# TR4.net
KiCad netlist of a schematic drawn in EAGLE
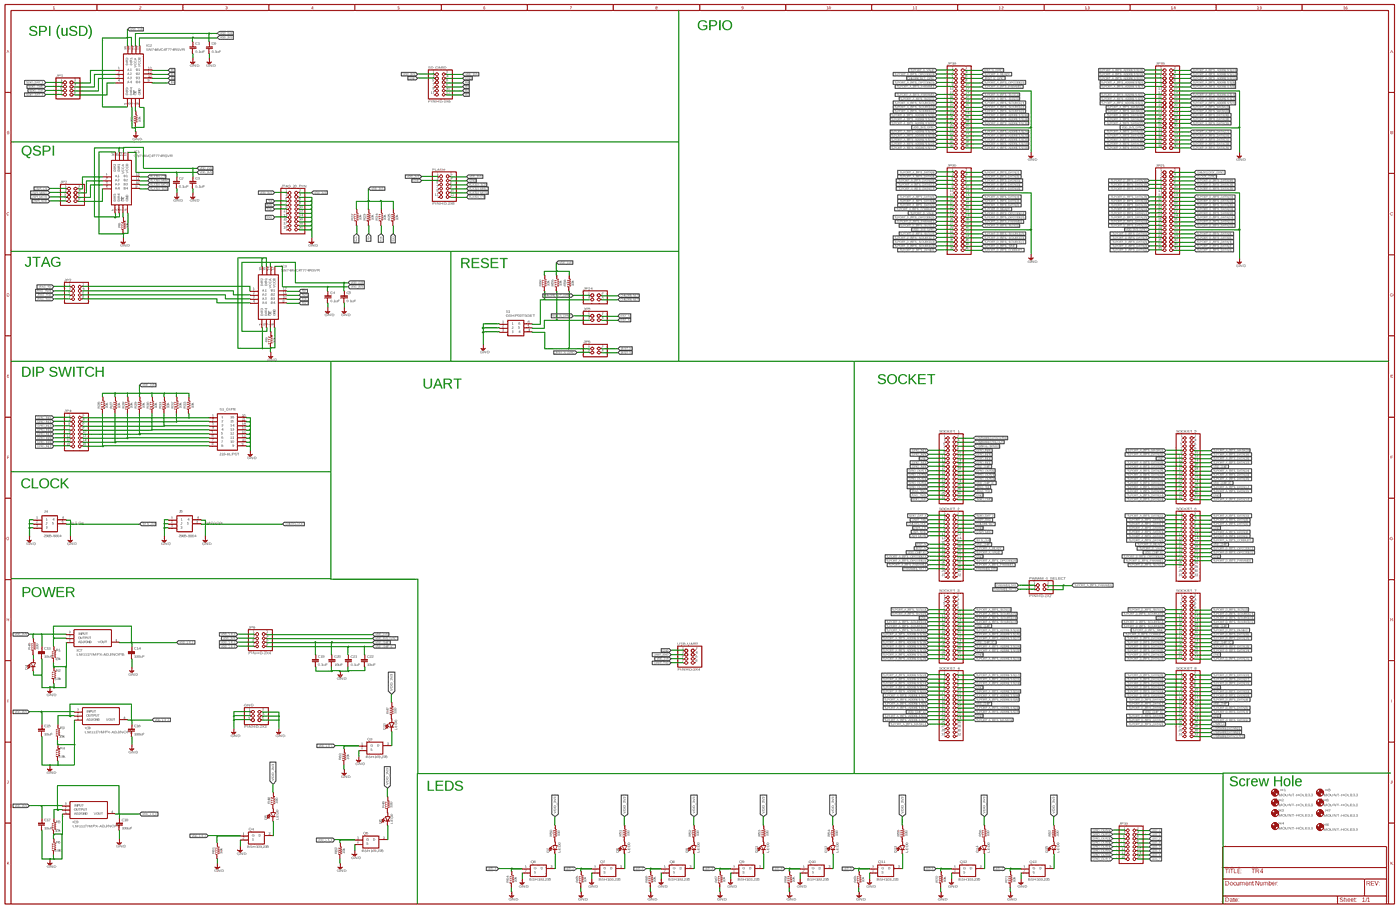
[diagram p0: schematic, sheet 1, overview]
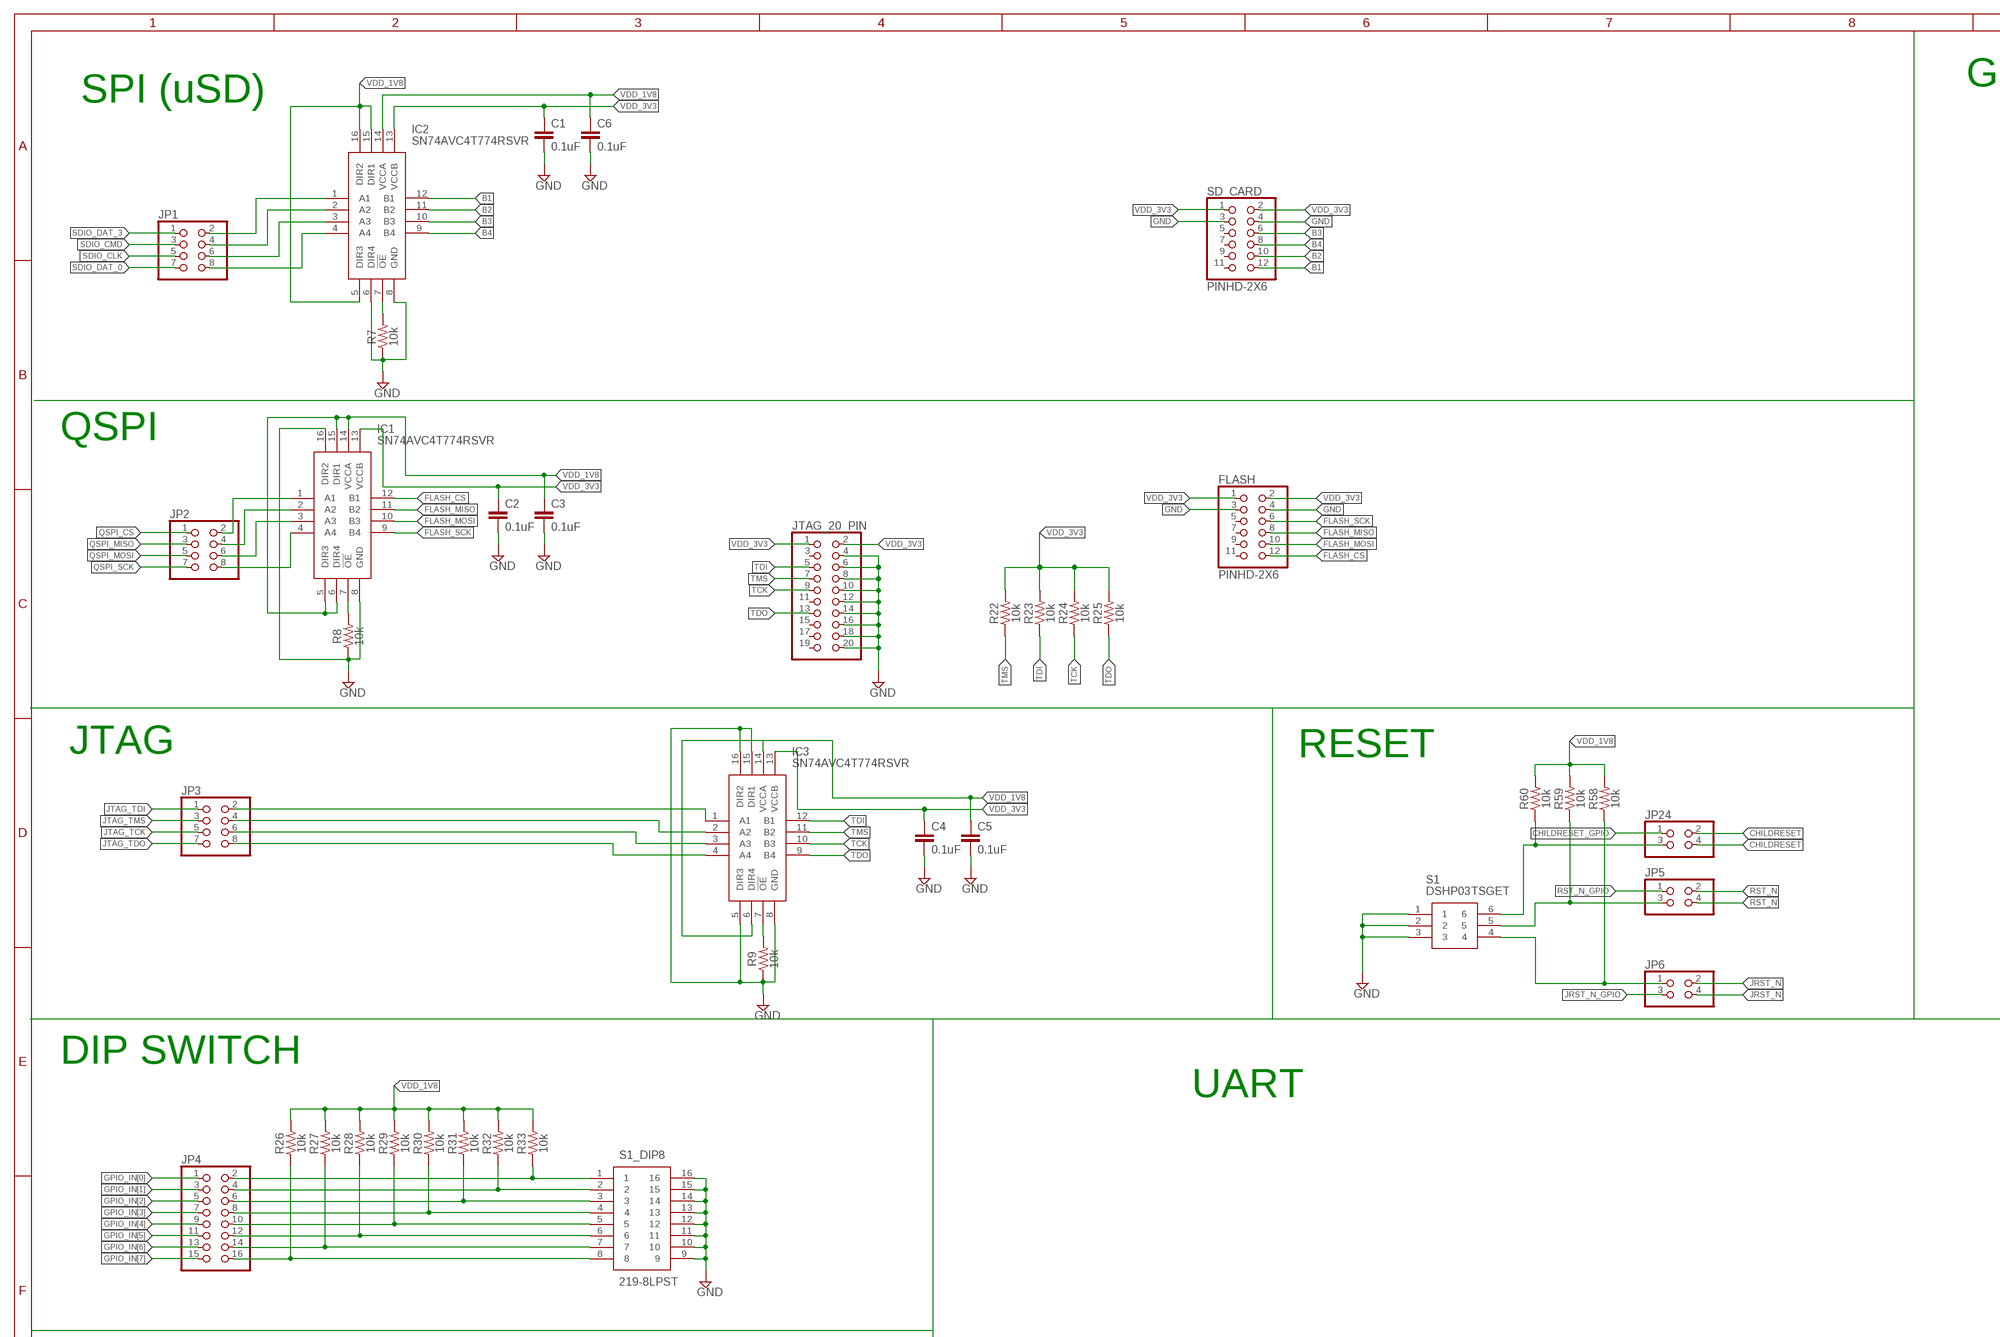
[diagram p1: schematic, sheet 1, part 1 of 4]
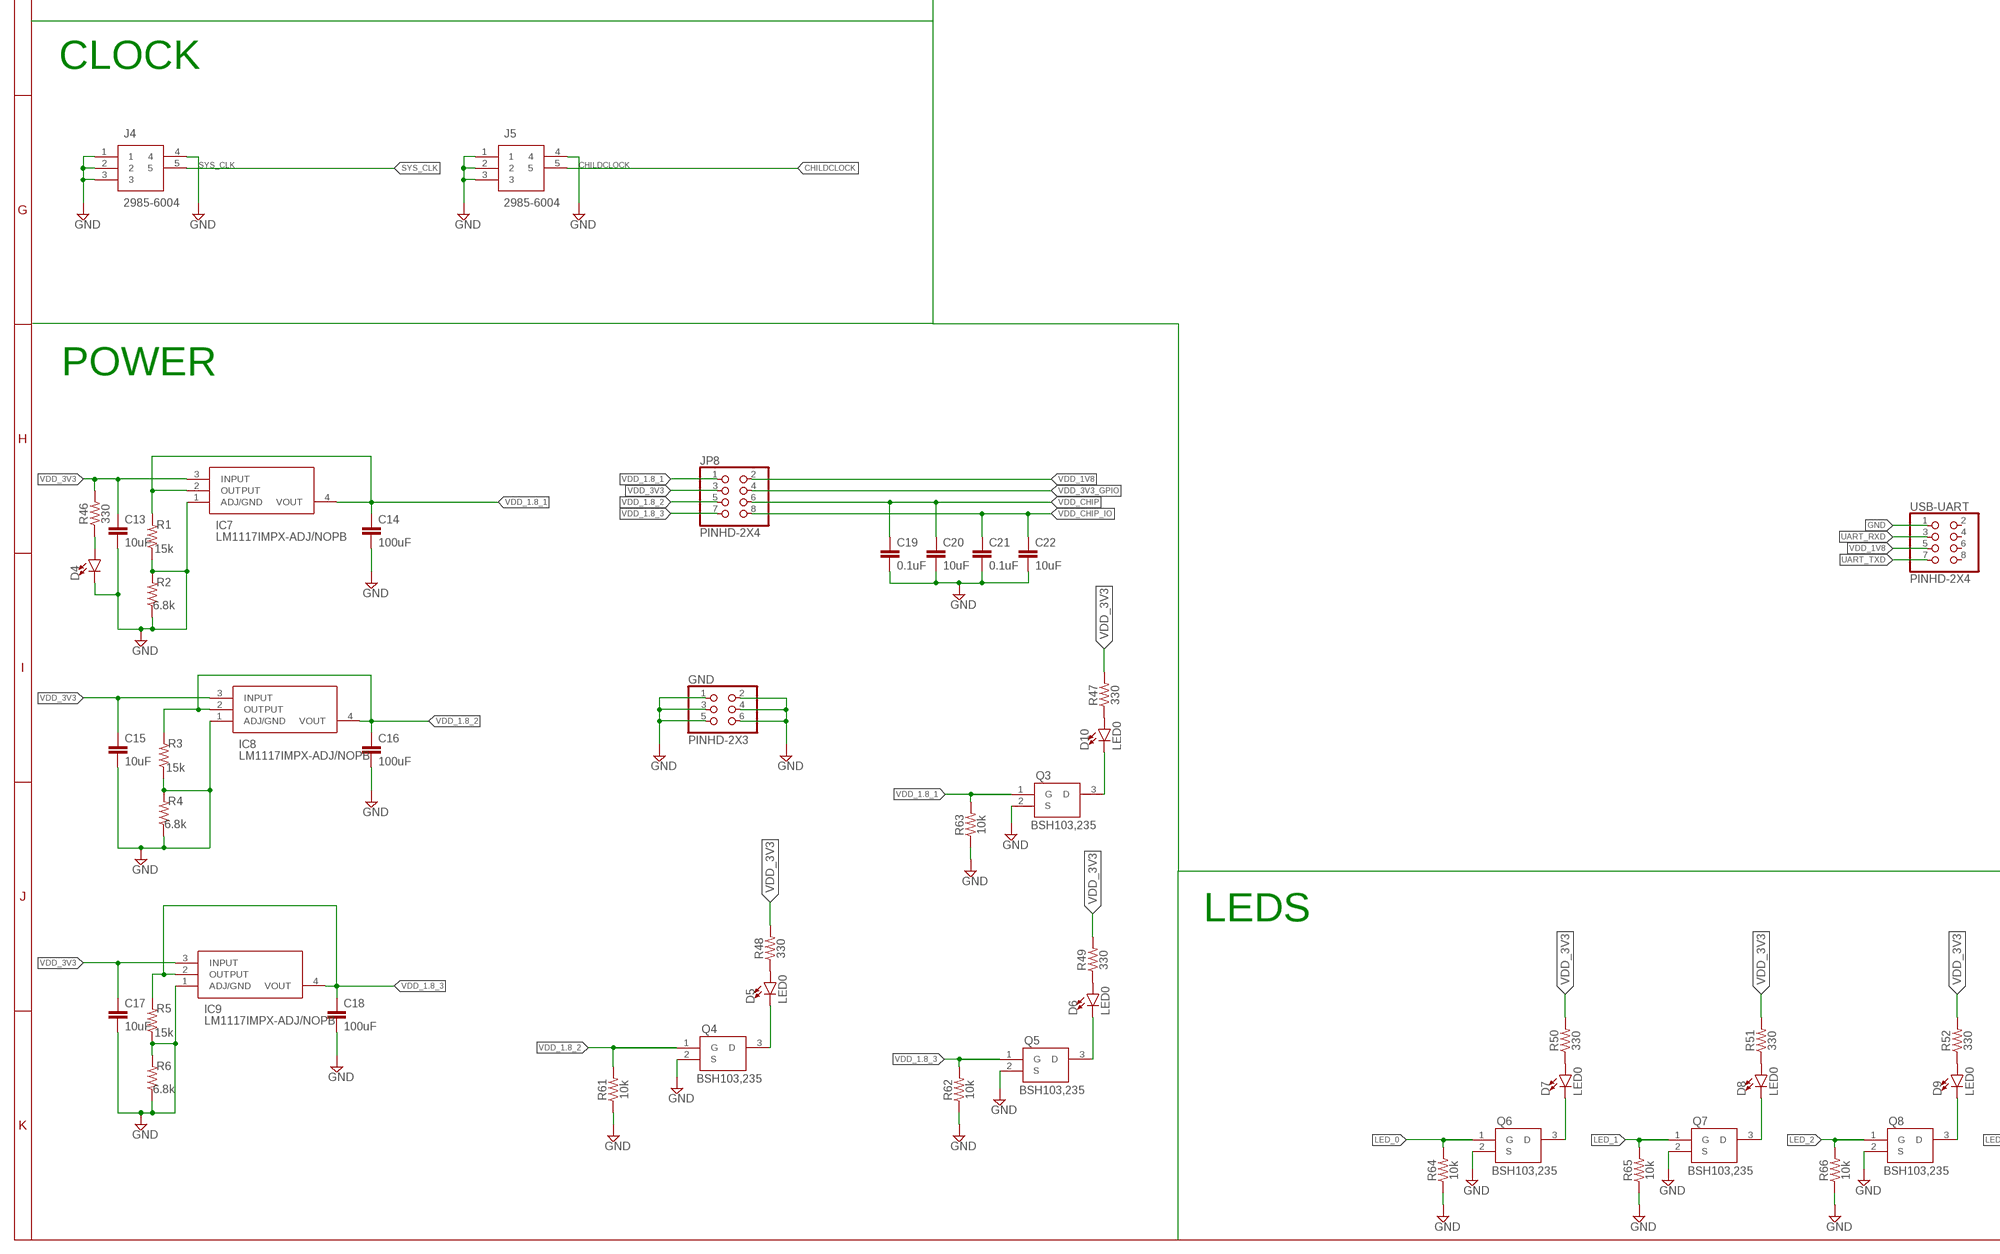
[diagram p2: schematic, sheet 1, part 2 of 4]
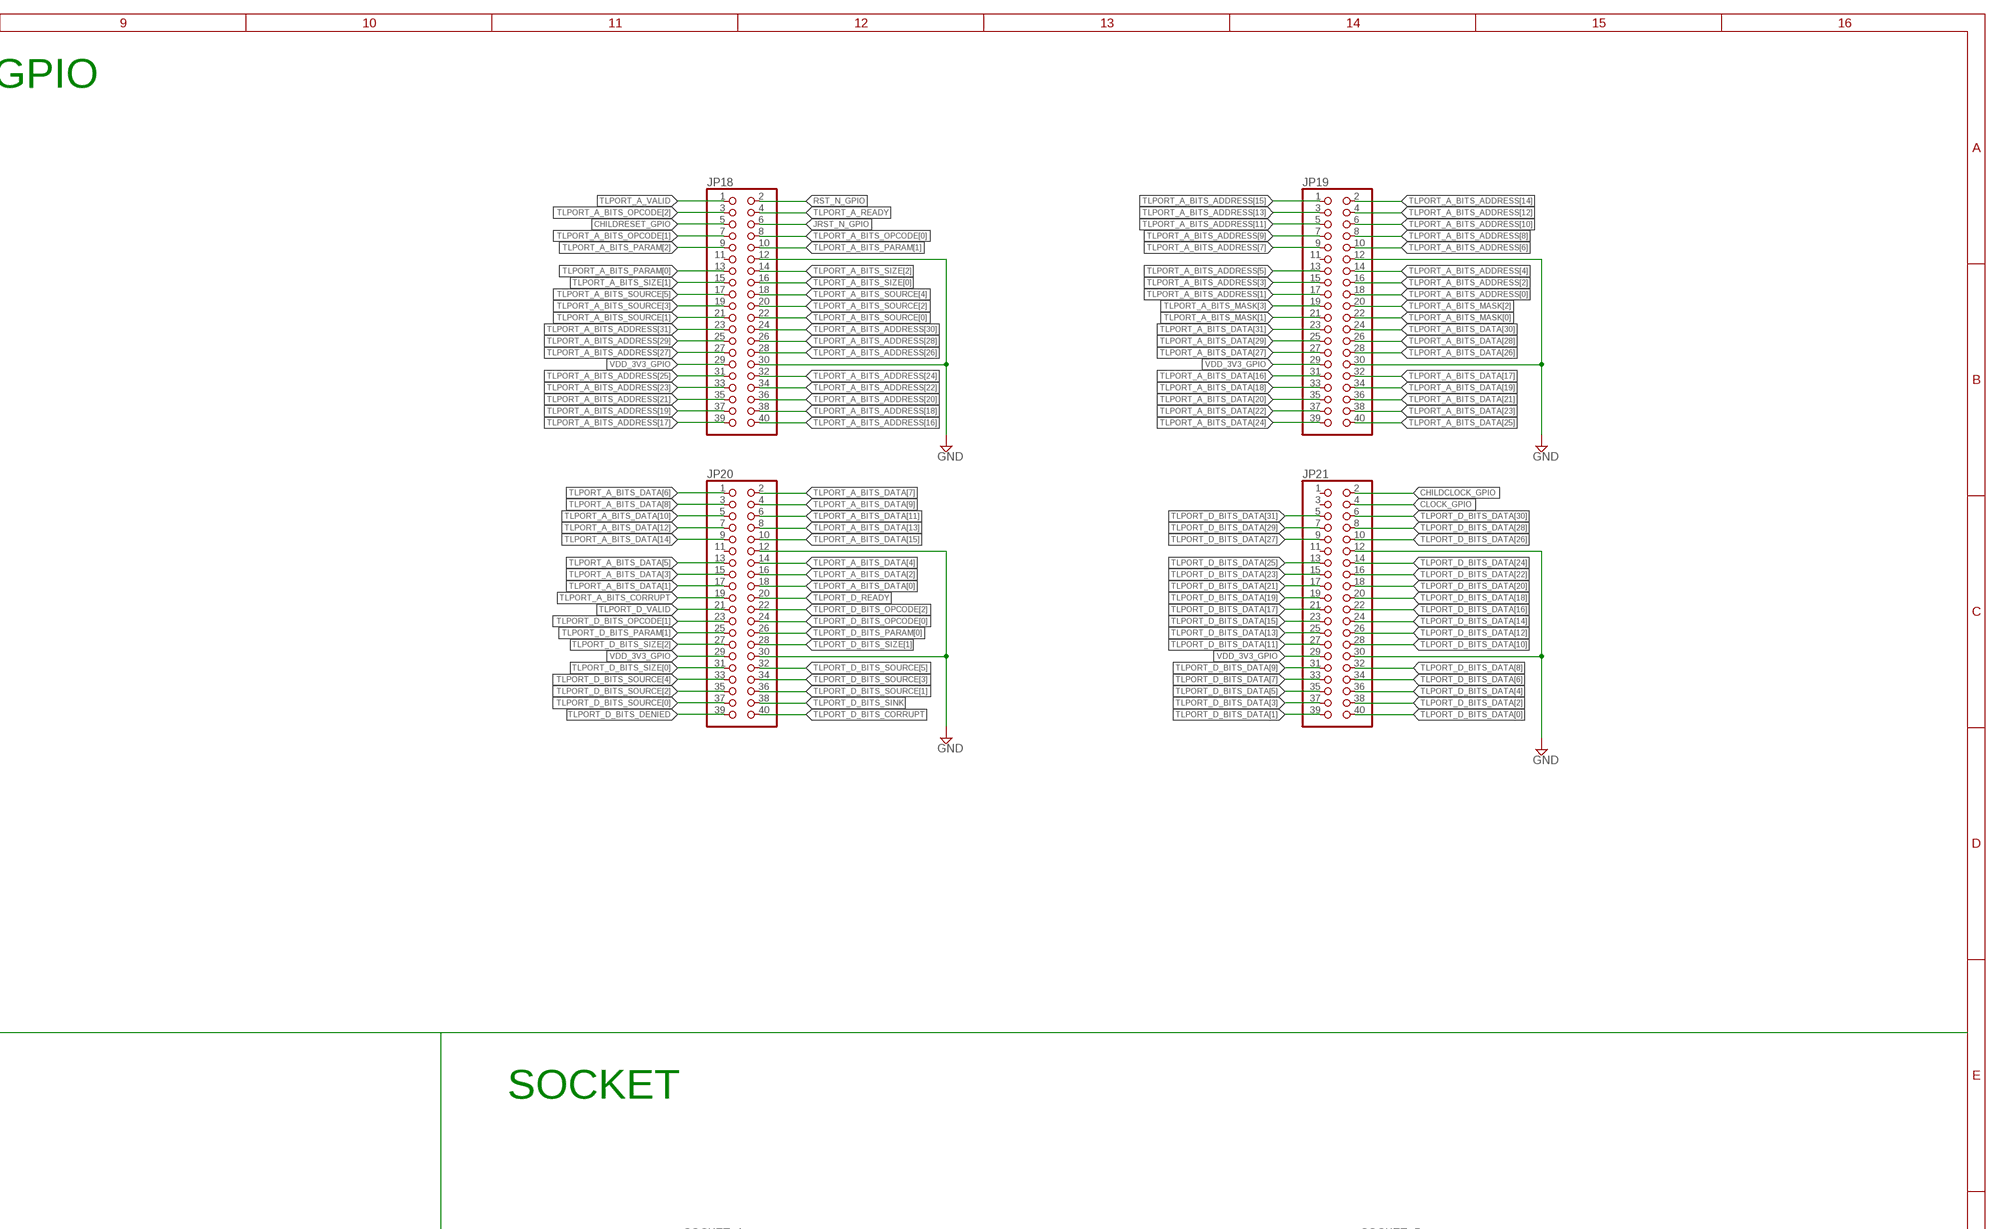
[diagram p3: schematic, sheet 1, part 3 of 4]
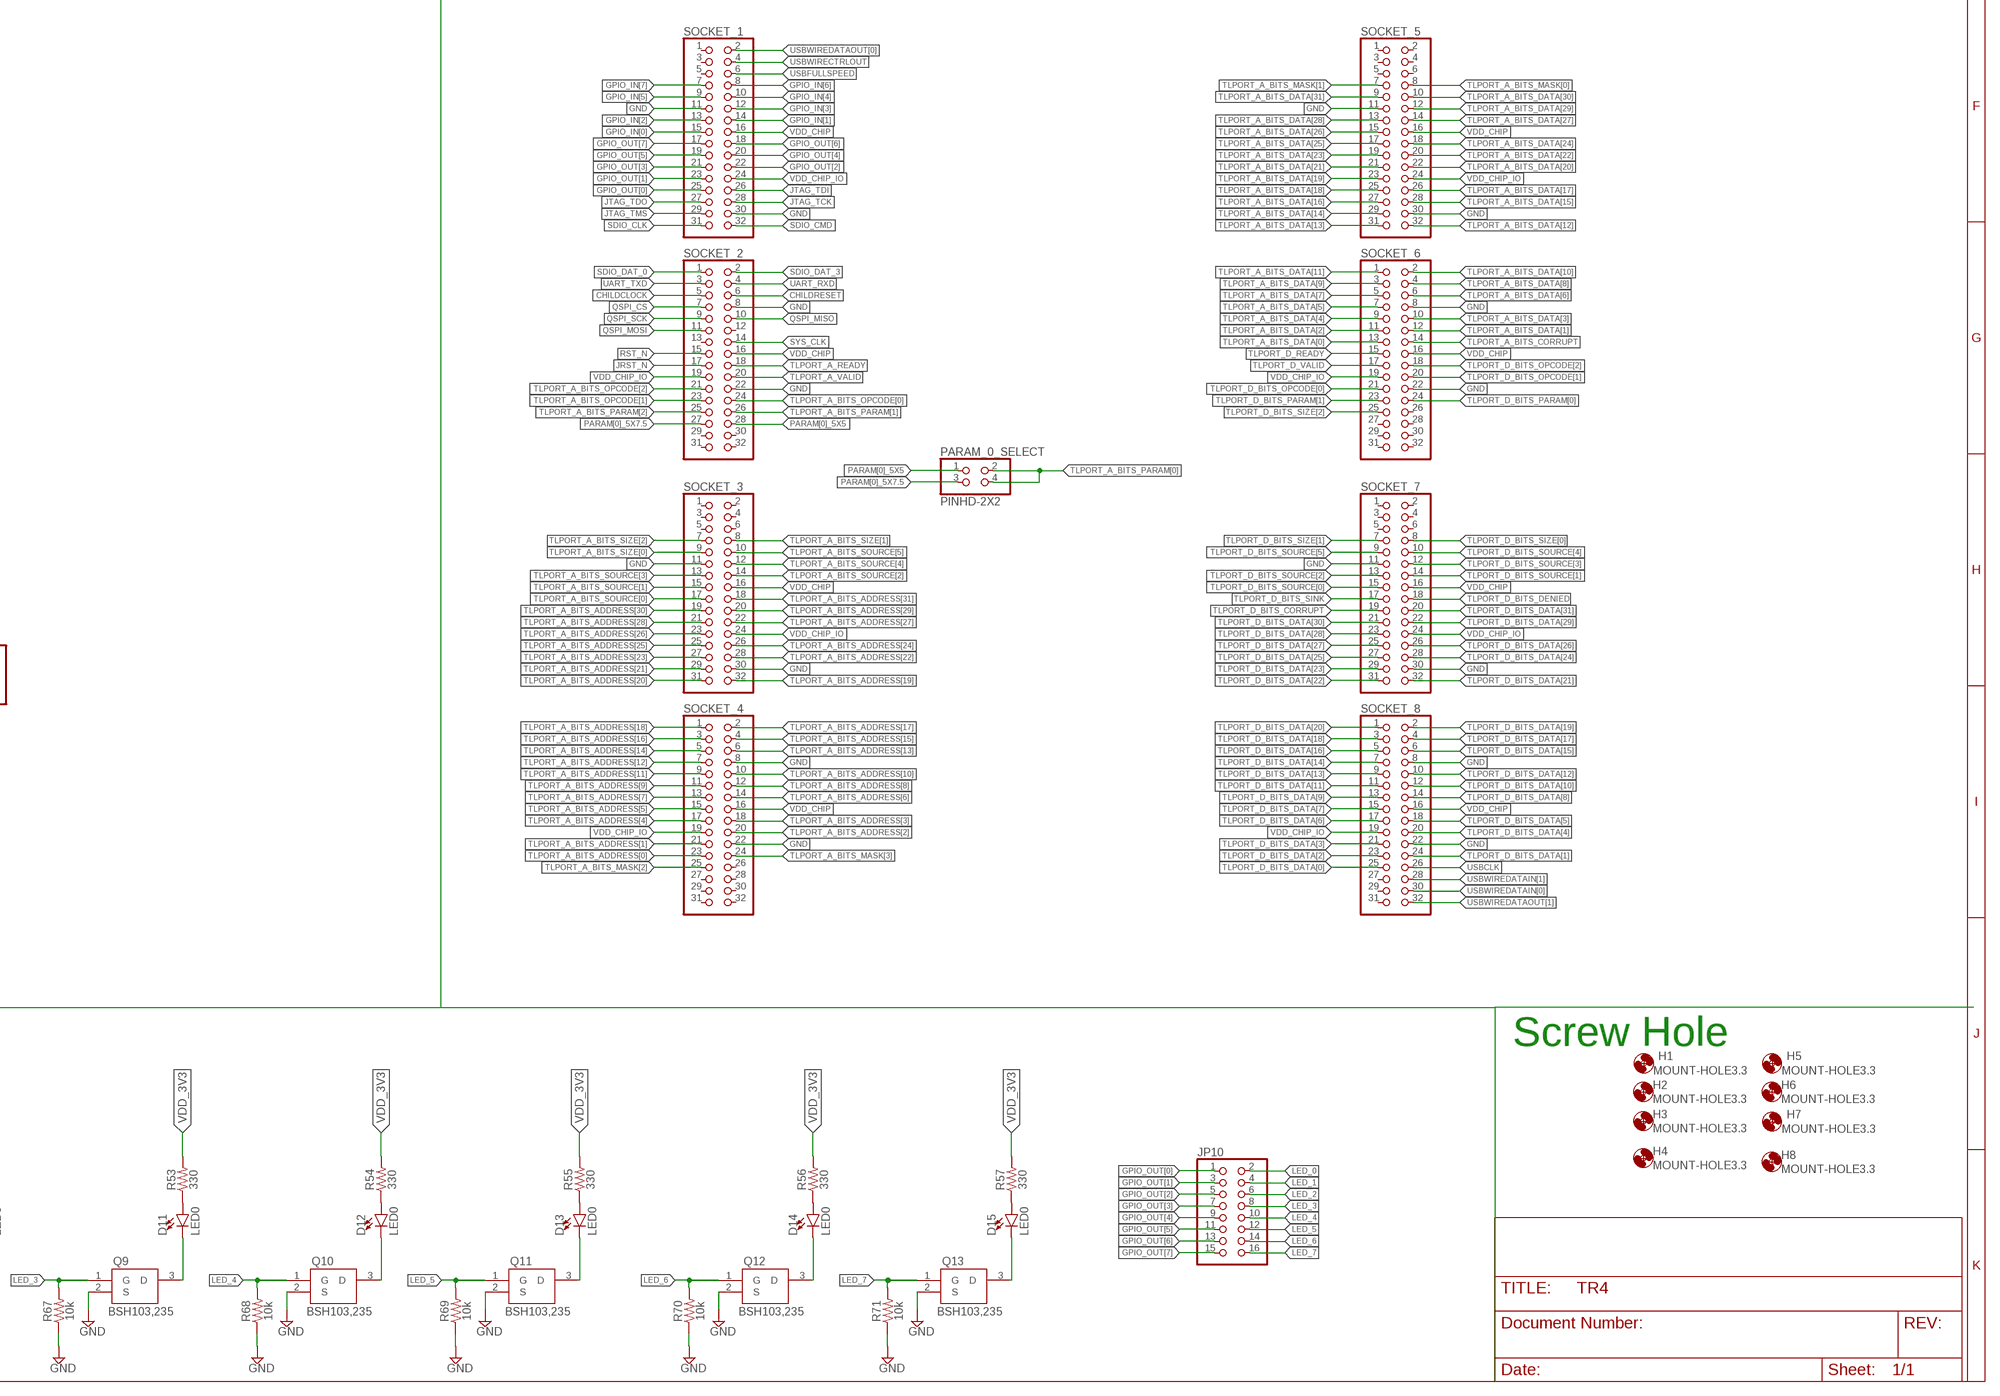
[diagram p4: schematic, sheet 1, part 4 of 4]

(export (version "E")
  (design (tool "Eeschema 10.0.6"))
  (components
    (comp (ref "C1")
      (value "0.1uF")
      (footprint "eagle-import:0603")
      (libsource (lib "eagle-import") (part "0.1UF-0603-25V-5%"))
    )
    (comp (ref "C2")
      (value "0.1uF")
      (footprint "eagle-import:0603")
      (libsource (lib "eagle-import") (part "0.1UF-0603-25V-5%"))
    )
    (comp (ref "C3")
      (value "0.1uF")
      (footprint "eagle-import:0603")
      (libsource (lib "eagle-import") (part "0.1UF-0603-25V-5%"))
    )
    (comp (ref "C4")
      (value "0.1uF")
      (footprint "eagle-import:0603")
      (libsource (lib "eagle-import") (part "0.1UF-0603-25V-5%"))
    )
    (comp (ref "C5")
      (value "0.1uF")
      (footprint "eagle-import:0603")
      (libsource (lib "eagle-import") (part "0.1UF-0603-25V-5%"))
    )
    (comp (ref "C6")
      (value "0.1uF")
      (footprint "eagle-import:0603")
      (libsource (lib "eagle-import") (part "0.1UF-0603-25V-5%"))
    )
    (comp (ref "C13")
      (value "10uF")
      (footprint "eagle-import:0603")
      (libsource (lib "eagle-import") (part "10UF-0603-6.3V-20%"))
    )
    (comp (ref "C14")
      (value "100uF")
      (footprint "eagle-import:0603")
      (libsource (lib "eagle-import") (part "10UF-0603-6.3V-20%"))
    )
    (comp (ref "C15")
      (value "10uF")
      (footprint "eagle-import:0603")
      (libsource (lib "eagle-import") (part "10UF-0603-6.3V-20%"))
    )
    (comp (ref "C16")
      (value "100uF")
      (footprint "eagle-import:0603")
      (libsource (lib "eagle-import") (part "10UF-0603-6.3V-20%"))
    )
    (comp (ref "C17")
      (value "10uF")
      (footprint "eagle-import:0603")
      (libsource (lib "eagle-import") (part "10UF-0603-6.3V-20%"))
    )
    (comp (ref "C18")
      (value "100uF")
      (footprint "eagle-import:0603")
      (libsource (lib "eagle-import") (part "10UF-0603-6.3V-20%"))
    )
    (comp (ref "C19")
      (value "0.1uF")
      (footprint "eagle-import:0603")
      (libsource (lib "eagle-import") (part "0.1UF-0603-25V-5%"))
    )
    (comp (ref "C20")
      (value "10uF")
      (footprint "eagle-import:0603")
      (libsource (lib "eagle-import") (part "10UF-0603-6.3V-20%"))
    )
    (comp (ref "C21")
      (value "0.1uF")
      (footprint "eagle-import:0603")
      (libsource (lib "eagle-import") (part "0.1UF-0603-25V-5%"))
    )
    (comp (ref "C22")
      (value "10uF")
      (footprint "eagle-import:0603")
      (libsource (lib "eagle-import") (part "10UF-0603-6.3V-20%"))
    )
    (comp (ref "D4")
      (value "LED0603")
      (footprint "eagle-import:LED-0603")
      (libsource (lib "eagle-import") (part "LED0603"))
    )
    (comp (ref "D5")
      (value "LED0")
      (footprint "eagle-import:LED-0603")
      (libsource (lib "eagle-import") (part "LED0603"))
    )
    (comp (ref "D6")
      (value "LED0")
      (footprint "eagle-import:LED-0603")
      (libsource (lib "eagle-import") (part "LED0603"))
    )
    (comp (ref "D7")
      (value "LED0")
      (footprint "eagle-import:LED-0603")
      (libsource (lib "eagle-import") (part "LED0603"))
    )
    (comp (ref "D8")
      (value "LED0")
      (footprint "eagle-import:LED-0603")
      (libsource (lib "eagle-import") (part "LED0603"))
    )
    (comp (ref "D9")
      (value "LED0")
      (footprint "eagle-import:LED-0603")
      (libsource (lib "eagle-import") (part "LED0603"))
    )
    (comp (ref "D10")
      (value "LED0")
      (footprint "eagle-import:LED-0603")
      (libsource (lib "eagle-import") (part "LED0603"))
    )
    (comp (ref "D11")
      (value "LED0")
      (footprint "eagle-import:LED-0603")
      (libsource (lib "eagle-import") (part "LED0603"))
    )
    (comp (ref "D12")
      (value "LED0")
      (footprint "eagle-import:LED-0603")
      (libsource (lib "eagle-import") (part "LED0603"))
    )
    (comp (ref "D13")
      (value "LED0")
      (footprint "eagle-import:LED-0603")
      (libsource (lib "eagle-import") (part "LED0603"))
    )
    (comp (ref "D14")
      (value "LED0")
      (footprint "eagle-import:LED-0603")
      (libsource (lib "eagle-import") (part "LED0603"))
    )
    (comp (ref "D15")
      (value "LED0")
      (footprint "eagle-import:LED-0603")
      (libsource (lib "eagle-import") (part "LED0603"))
    )
    (comp (ref "FLASH")
      (value "PINHD-2X6")
      (footprint "eagle-import:2X06")
      (libsource (lib "eagle-import") (part "PINHD-2X6"))
    )
    (comp (ref "GND")
      (value "PINHD-2X3")
      (footprint "eagle-import:2X03")
      (libsource (lib "eagle-import") (part "PINHD-2X3"))
    )
    (comp (ref "H1")
      (value "MOUNT-HOLE3.3")
      (footprint "eagle-import:3,3")
      (libsource (lib "eagle-import") (part "MOUNT-HOLE3.3"))
    )
    (comp (ref "H2")
      (value "MOUNT-HOLE3.3")
      (footprint "eagle-import:3,3")
      (libsource (lib "eagle-import") (part "MOUNT-HOLE3.3"))
    )
    (comp (ref "H3")
      (value "MOUNT-HOLE3.3")
      (footprint "eagle-import:3,3")
      (libsource (lib "eagle-import") (part "MOUNT-HOLE3.3"))
    )
    (comp (ref "H4")
      (value "MOUNT-HOLE3.3")
      (footprint "eagle-import:3,3")
      (libsource (lib "eagle-import") (part "MOUNT-HOLE3.3"))
    )
    (comp (ref "H5")
      (value "MOUNT-HOLE3.3")
      (footprint "eagle-import:3,3")
      (libsource (lib "eagle-import") (part "MOUNT-HOLE3.3"))
    )
    (comp (ref "H6")
      (value "MOUNT-HOLE3.3")
      (footprint "eagle-import:3,3")
      (libsource (lib "eagle-import") (part "MOUNT-HOLE3.3"))
    )
    (comp (ref "H7")
      (value "MOUNT-HOLE3.3")
      (footprint "eagle-import:3,3")
      (libsource (lib "eagle-import") (part "MOUNT-HOLE3.3"))
    )
    (comp (ref "H8")
      (value "MOUNT-HOLE3.3")
      (footprint "eagle-import:3,3")
      (libsource (lib "eagle-import") (part "MOUNT-HOLE3.3"))
    )
    (comp (ref "IC1")
      (value "SN74AVC4T774RSVR")
      (footprint "eagle-import:QFN40P180X260X55-16N")
      (fields (field (name "MOUSER_PART_NUMBER") "595-SN74AVC4T774RSVR"))
      (libsource (lib "eagle-import") (part "SN74AVC4T774RSVR"))
    )
    (comp (ref "IC2")
      (value "SN74AVC4T774RSVR")
      (footprint "eagle-import:QFN40P180X260X55-16N")
      (fields (field (name "MOUSER_PART_NUMBER") "595-SN74AVC4T774RSVR"))
      (libsource (lib "eagle-import") (part "SN74AVC4T774RSVR"))
    )
    (comp (ref "IC3")
      (value "SN74AVC4T774RSVR")
      (footprint "eagle-import:QFN40P180X260X55-16N")
      (fields (field (name "MOUSER_PART_NUMBER") "595-SN74AVC4T774RSVR"))
      (libsource (lib "eagle-import") (part "SN74AVC4T774RSVR"))
    )
    (comp (ref "IC7")
      (value "LM1117IMPX-ADJ/NOPB")
      (footprint "eagle-import:SOT230P700X180-4N")
      (fields
        (field (name "ARROW_PART_NUMBER") "LM1117MP-1.8/NOPB")
        (field (name "MOUSER_PART_NUMBER") "926-LM1117MP-1.8NOPB")
      )
      (libsource (lib "eagle-import") (part "LM1117MP-1.8_NOPB"))
    )
    (comp (ref "IC8")
      (value "LM1117IMPX-ADJ/NOPB")
      (footprint "eagle-import:SOT230P700X180-4N")
      (fields
        (field (name "ARROW_PART_NUMBER") "LM1117MP-1.8/NOPB")
        (field (name "MOUSER_PART_NUMBER") "926-LM1117MP-1.8NOPB")
      )
      (libsource (lib "eagle-import") (part "LM1117MP-1.8_NOPB"))
    )
    (comp (ref "IC9")
      (value "LM1117IMPX-ADJ/NOPB")
      (footprint "eagle-import:SOT230P700X180-4N")
      (fields
        (field (name "ARROW_PART_NUMBER") "LM1117MP-1.8/NOPB")
        (field (name "MOUSER_PART_NUMBER") "926-LM1117MP-1.8NOPB")
      )
      (libsource (lib "eagle-import") (part "LM1117MP-1.8_NOPB"))
    )
    (comp (ref "J4")
      (value "2985-6004")
      (footprint "eagle-import:29856004")
      (fields (field (name "MOUSER_PART_NUMBER") "523-2985-6004"))
      (libsource (lib "eagle-import") (part "2985-6004"))
    )
    (comp (ref "J5")
      (value "2985-6004")
      (footprint "eagle-import:29856004")
      (fields (field (name "MOUSER_PART_NUMBER") "523-2985-6004"))
      (libsource (lib "eagle-import") (part "2985-6004"))
    )
    (comp (ref "JP1")
      (value "PINHD-2X4")
      (footprint "eagle-import:2X04")
      (libsource (lib "eagle-import") (part "adafruit_420_PINHD-2X4"))
    )
    (comp (ref "JP2")
      (value "PINHD-2X4")
      (footprint "eagle-import:2X04")
      (libsource (lib "eagle-import") (part "adafruit_420_PINHD-2X4"))
    )
    (comp (ref "JP3")
      (value "PINHD-2X4")
      (footprint "eagle-import:2X04")
      (libsource (lib "eagle-import") (part "adafruit_420_PINHD-2X4"))
    )
    (comp (ref "JP4")
      (value "PINHD-2X8")
      (footprint "eagle-import:2X08")
      (libsource (lib "eagle-import") (part "PINHD-2X8"))
    )
    (comp (ref "JP5")
      (value "PINHD-2X2")
      (footprint "eagle-import:2X02")
      (libsource (lib "eagle-import") (part "pinhead_325_PINHD-2X2"))
    )
    (comp (ref "JP6")
      (value "PINHD-2X2")
      (footprint "eagle-import:2X02")
      (libsource (lib "eagle-import") (part "pinhead_325_PINHD-2X2"))
    )
    (comp (ref "JP8")
      (value "PINHD-2X4")
      (footprint "eagle-import:2X04")
      (libsource (lib "eagle-import") (part "PINHD-2X4"))
    )
    (comp (ref "JP10")
      (value "PINHD-2X8")
      (footprint "eagle-import:2X08")
      (libsource (lib "eagle-import") (part "PINHD-2X8"))
    )
    (comp (ref "JP18")
      (value "PINHD-2X20")
      (footprint "eagle-import:2X20")
      (libsource (lib "eagle-import") (part "PINHD-2X20"))
    )
    (comp (ref "JP19")
      (value "PINHD-2X20")
      (footprint "eagle-import:2X20")
      (libsource (lib "eagle-import") (part "PINHD-2X20"))
    )
    (comp (ref "JP20")
      (value "PINHD-2X20")
      (footprint "eagle-import:2X20")
      (libsource (lib "eagle-import") (part "PINHD-2X20"))
    )
    (comp (ref "JP21")
      (value "PINHD-2X20")
      (footprint "eagle-import:2X20")
      (libsource (lib "eagle-import") (part "PINHD-2X20"))
    )
    (comp (ref "JP24")
      (value "PINHD-2X2")
      (footprint "eagle-import:2X02")
      (libsource (lib "eagle-import") (part "pinhead_325_PINHD-2X2"))
    )
    (comp (ref "JTAG_20_PIN")
      (value "PINHD-2X10")
      (footprint "eagle-import:2X10")
      (libsource (lib "eagle-import") (part "PINHD-2X10"))
    )
    (comp (ref "PARAM_0_SELECT")
      (value "PINHD-2X2")
      (footprint "eagle-import:2X02")
      (libsource (lib "eagle-import") (part "PINHD-2X2"))
    )
    (comp (ref "Q3")
      (value "BSH103,235")
      (footprint "eagle-import:SOT95P230X110-3N")
      (fields (field (name "MOUSER_PART_NUMBER") "771-BSH103235"))
      (libsource (lib "eagle-import") (part "BSH103,235"))
    )
    (comp (ref "Q4")
      (value "BSH103,235")
      (footprint "eagle-import:SOT95P230X110-3N")
      (fields (field (name "MOUSER_PART_NUMBER") "771-BSH103235"))
      (libsource (lib "eagle-import") (part "BSH103,235"))
    )
    (comp (ref "Q5")
      (value "BSH103,235")
      (footprint "eagle-import:SOT95P230X110-3N")
      (fields (field (name "MOUSER_PART_NUMBER") "771-BSH103235"))
      (libsource (lib "eagle-import") (part "BSH103,235"))
    )
    (comp (ref "Q6")
      (value "BSH103,235")
      (footprint "eagle-import:SOT95P230X110-3N")
      (fields (field (name "MOUSER_PART_NUMBER") "771-BSH103235"))
      (libsource (lib "eagle-import") (part "BSH103,235"))
    )
    (comp (ref "Q7")
      (value "BSH103,235")
      (footprint "eagle-import:SOT95P230X110-3N")
      (fields (field (name "MOUSER_PART_NUMBER") "771-BSH103235"))
      (libsource (lib "eagle-import") (part "BSH103,235"))
    )
    (comp (ref "Q8")
      (value "BSH103,235")
      (footprint "eagle-import:SOT95P230X110-3N")
      (fields (field (name "MOUSER_PART_NUMBER") "771-BSH103235"))
      (libsource (lib "eagle-import") (part "BSH103,235"))
    )
    (comp (ref "Q9")
      (value "BSH103,235")
      (footprint "eagle-import:SOT95P230X110-3N")
      (fields (field (name "MOUSER_PART_NUMBER") "771-BSH103235"))
      (libsource (lib "eagle-import") (part "BSH103,235"))
    )
    (comp (ref "Q10")
      (value "BSH103,235")
      (footprint "eagle-import:SOT95P230X110-3N")
      (fields (field (name "MOUSER_PART_NUMBER") "771-BSH103235"))
      (libsource (lib "eagle-import") (part "BSH103,235"))
    )
    (comp (ref "Q11")
      (value "BSH103,235")
      (footprint "eagle-import:SOT95P230X110-3N")
      (fields (field (name "MOUSER_PART_NUMBER") "771-BSH103235"))
      (libsource (lib "eagle-import") (part "BSH103,235"))
    )
    (comp (ref "Q12")
      (value "BSH103,235")
      (footprint "eagle-import:SOT95P230X110-3N")
      (fields (field (name "MOUSER_PART_NUMBER") "771-BSH103235"))
      (libsource (lib "eagle-import") (part "BSH103,235"))
    )
    (comp (ref "Q13")
      (value "BSH103,235")
      (footprint "eagle-import:SOT95P230X110-3N")
      (fields (field (name "MOUSER_PART_NUMBER") "771-BSH103235"))
      (libsource (lib "eagle-import") (part "BSH103,235"))
    )
    (comp (ref "R1")
      (value "15k")
      (footprint "eagle-import:0603")
      (libsource (lib "eagle-import") (part "15KOHM-0603-1/10W-1%"))
    )
    (comp (ref "R2")
      (value "6.8k")
      (footprint "eagle-import:0603")
      (libsource (lib "eagle-import") (part "6.8KOHM-0603-1/10W-1%"))
    )
    (comp (ref "R3")
      (value "15k")
      (footprint "eagle-import:0603")
      (libsource (lib "eagle-import") (part "15KOHM-0603-1/10W-1%"))
    )
    (comp (ref "R4")
      (value "6.8k")
      (footprint "eagle-import:0603")
      (libsource (lib "eagle-import") (part "6.8KOHM-0603-1/10W-1%"))
    )
    (comp (ref "R5")
      (value "15k")
      (footprint "eagle-import:0603")
      (libsource (lib "eagle-import") (part "15KOHM-0603-1/10W-1%"))
    )
    (comp (ref "R6")
      (value "6.8k")
      (footprint "eagle-import:0603")
      (libsource (lib "eagle-import") (part "6.8KOHM-0603-1/10W-1%"))
    )
    (comp (ref "R7")
      (value "10k")
      (footprint "eagle-import:0603")
      (libsource (lib "eagle-import") (part "10KOHM-0603-1/10W-1%"))
    )
    (comp (ref "R8")
      (value "10k")
      (footprint "eagle-import:0603")
      (libsource (lib "eagle-import") (part "10KOHM-0603-1/10W-1%"))
    )
    (comp (ref "R9")
      (value "10k")
      (footprint "eagle-import:0603")
      (libsource (lib "eagle-import") (part "10KOHM-0603-1/10W-1%"))
    )
    (comp (ref "R22")
      (value "10k")
      (footprint "eagle-import:0603")
      (libsource (lib "eagle-import") (part "10KOHM-0603-1/10W-1%"))
    )
    (comp (ref "R23")
      (value "10k")
      (footprint "eagle-import:0603")
      (libsource (lib "eagle-import") (part "10KOHM-0603-1/10W-1%"))
    )
    (comp (ref "R24")
      (value "10k")
      (footprint "eagle-import:0603")
      (libsource (lib "eagle-import") (part "10KOHM-0603-1/10W-1%"))
    )
    (comp (ref "R25")
      (value "10k")
      (footprint "eagle-import:0603")
      (libsource (lib "eagle-import") (part "10KOHM-0603-1/10W-1%"))
    )
    (comp (ref "R26")
      (value "10k")
      (footprint "eagle-import:0603")
      (libsource (lib "eagle-import") (part "10KOHM-0603-1/10W-1%"))
    )
    (comp (ref "R27")
      (value "10k")
      (footprint "eagle-import:0603")
      (libsource (lib "eagle-import") (part "10KOHM-0603-1/10W-1%"))
    )
    (comp (ref "R28")
      (value "10k")
      (footprint "eagle-import:0603")
      (libsource (lib "eagle-import") (part "10KOHM-0603-1/10W-1%"))
    )
    (comp (ref "R29")
      (value "10k")
      (footprint "eagle-import:0603")
      (libsource (lib "eagle-import") (part "10KOHM-0603-1/10W-1%"))
    )
    (comp (ref "R30")
      (value "10k")
      (footprint "eagle-import:0603")
      (libsource (lib "eagle-import") (part "10KOHM-0603-1/10W-1%"))
    )
    (comp (ref "R31")
      (value "10k")
      (footprint "eagle-import:0603")
      (libsource (lib "eagle-import") (part "10KOHM-0603-1/10W-1%"))
    )
    (comp (ref "R32")
      (value "10k")
      (footprint "eagle-import:0603")
      (libsource (lib "eagle-import") (part "10KOHM-0603-1/10W-1%"))
    )
    (comp (ref "R33")
      (value "10k")
      (footprint "eagle-import:0603")
      (libsource (lib "eagle-import") (part "10KOHM-0603-1/10W-1%"))
    )
    (comp (ref "R46")
      (value "330")
      (footprint "eagle-import:0603")
      (libsource (lib "eagle-import") (part "330OHM-0603-1/10W-1%"))
    )
    (comp (ref "R47")
      (value "330")
      (footprint "eagle-import:0603")
      (libsource (lib "eagle-import") (part "330OHM-0603-1/10W-1%"))
    )
    (comp (ref "R48")
      (value "330")
      (footprint "eagle-import:0603")
      (libsource (lib "eagle-import") (part "330OHM-0603-1/10W-1%"))
    )
    (comp (ref "R49")
      (value "330")
      (footprint "eagle-import:0603")
      (libsource (lib "eagle-import") (part "330OHM-0603-1/10W-1%"))
    )
    (comp (ref "R50")
      (value "330")
      (footprint "eagle-import:0603")
      (libsource (lib "eagle-import") (part "330OHM-0603-1/10W-1%"))
    )
    (comp (ref "R51")
      (value "330")
      (footprint "eagle-import:0603")
      (libsource (lib "eagle-import") (part "330OHM-0603-1/10W-1%"))
    )
    (comp (ref "R52")
      (value "330")
      (footprint "eagle-import:0603")
      (libsource (lib "eagle-import") (part "330OHM-0603-1/10W-1%"))
    )
    (comp (ref "R53")
      (value "330")
      (footprint "eagle-import:0603")
      (libsource (lib "eagle-import") (part "330OHM-0603-1/10W-1%"))
    )
    (comp (ref "R54")
      (value "330")
      (footprint "eagle-import:0603")
      (libsource (lib "eagle-import") (part "330OHM-0603-1/10W-1%"))
    )
    (comp (ref "R55")
      (value "330")
      (footprint "eagle-import:0603")
      (libsource (lib "eagle-import") (part "330OHM-0603-1/10W-1%"))
    )
    (comp (ref "R56")
      (value "330")
      (footprint "eagle-import:0603")
      (libsource (lib "eagle-import") (part "330OHM-0603-1/10W-1%"))
    )
    (comp (ref "R57")
      (value "330")
      (footprint "eagle-import:0603")
      (libsource (lib "eagle-import") (part "330OHM-0603-1/10W-1%"))
    )
    (comp (ref "R58")
      (value "10k")
      (footprint "eagle-import:0603")
      (libsource (lib "eagle-import") (part "10KOHM-0603-1/10W-1%"))
    )
    (comp (ref "R59")
      (value "10k")
      (footprint "eagle-import:0603")
      (libsource (lib "eagle-import") (part "10KOHM-0603-1/10W-1%"))
    )
    (comp (ref "R60")
      (value "10k")
      (footprint "eagle-import:0603")
      (libsource (lib "eagle-import") (part "10KOHM-0603-1/10W-1%"))
    )
    (comp (ref "R61")
      (value "10k")
      (footprint "eagle-import:0603")
      (libsource (lib "eagle-import") (part "10KOHM-0603-1/10W-1%"))
    )
    (comp (ref "R62")
      (value "10k")
      (footprint "eagle-import:0603")
      (libsource (lib "eagle-import") (part "10KOHM-0603-1/10W-1%"))
    )
    (comp (ref "R63")
      (value "10k")
      (footprint "eagle-import:0603")
      (libsource (lib "eagle-import") (part "10KOHM-0603-1/10W-1%"))
    )
    (comp (ref "R64")
      (value "10k")
      (footprint "eagle-import:0603")
      (libsource (lib "eagle-import") (part "10KOHM-0603-1/10W-1%"))
    )
    (comp (ref "R65")
      (value "10k")
      (footprint "eagle-import:0603")
      (libsource (lib "eagle-import") (part "10KOHM-0603-1/10W-1%"))
    )
    (comp (ref "R66")
      (value "10k")
      (footprint "eagle-import:0603")
      (libsource (lib "eagle-import") (part "10KOHM-0603-1/10W-1%"))
    )
    (comp (ref "R67")
      (value "10k")
      (footprint "eagle-import:0603")
      (libsource (lib "eagle-import") (part "10KOHM-0603-1/10W-1%"))
    )
    (comp (ref "R68")
      (value "10k")
      (footprint "eagle-import:0603")
      (libsource (lib "eagle-import") (part "10KOHM-0603-1/10W-1%"))
    )
    (comp (ref "R69")
      (value "10k")
      (footprint "eagle-import:0603")
      (libsource (lib "eagle-import") (part "10KOHM-0603-1/10W-1%"))
    )
    (comp (ref "R70")
      (value "10k")
      (footprint "eagle-import:0603")
      (libsource (lib "eagle-import") (part "10KOHM-0603-1/10W-1%"))
    )
    (comp (ref "R71")
      (value "10k")
      (footprint "eagle-import:0603")
      (libsource (lib "eagle-import") (part "10KOHM-0603-1/10W-1%"))
    )
    (comp (ref "S1")
      (value "DSHP03TSGET")
      (footprint "eagle-import:SOT127P835X260-6N")
      (libsource (lib "eagle-import") (part "DSHP03TSGET"))
    )
    (comp (ref "S1_DIP8")
      (value "219-8LPST")
      (footprint "eagle-import:2198LPST")
      (fields (field (name "MOUSER_PART_NUMBER") "774-2198LPST"))
      (libsource (lib "eagle-import") (part "219-8LPST"))
    )
    (comp (ref "SD_CARD")
      (value "PINHD-2X6")
      (footprint "eagle-import:2X06")
      (libsource (lib "eagle-import") (part "PINHD-2X6"))
    )
    (comp (ref "SOCKET_1")
      (value "PINHD-2X16")
      (footprint "eagle-import:2X16")
      (libsource (lib "eagle-import") (part "PINHD-2X16"))
    )
    (comp (ref "SOCKET_2")
      (value "PINHD-2X16")
      (footprint "eagle-import:2X16")
      (libsource (lib "eagle-import") (part "PINHD-2X16"))
    )
    (comp (ref "SOCKET_3")
      (value "PINHD-2X16")
      (footprint "eagle-import:2X16")
      (libsource (lib "eagle-import") (part "PINHD-2X16"))
    )
    (comp (ref "SOCKET_4")
      (value "PINHD-2X16")
      (footprint "eagle-import:2X16")
      (libsource (lib "eagle-import") (part "PINHD-2X16"))
    )
    (comp (ref "SOCKET_5")
      (value "PINHD-2X16")
      (footprint "eagle-import:2X16")
      (libsource (lib "eagle-import") (part "PINHD-2X16"))
    )
    (comp (ref "SOCKET_6")
      (value "PINHD-2X16")
      (footprint "eagle-import:2X16")
      (libsource (lib "eagle-import") (part "PINHD-2X16"))
    )
    (comp (ref "SOCKET_7")
      (value "PINHD-2X16")
      (footprint "eagle-import:2X16")
      (libsource (lib "eagle-import") (part "PINHD-2X16"))
    )
    (comp (ref "SOCKET_8")
      (value "PINHD-2X16")
      (footprint "eagle-import:2X16")
      (libsource (lib "eagle-import") (part "PINHD-2X16"))
    )
    (comp (ref "USB-UART")
      (value "PINHD-2X4")
      (footprint "eagle-import:2X04")
      (libsource (lib "eagle-import") (part "PINHD-2X4"))
    )
  )
  (nets
    (net (code "1") (name "B1") (class "Default")
      (node (ref "IC2") (pin "12") (pinfunction "B1_12") (pintype "bidirectional"))
      (node (ref "SD_CARD") (pin "12") (pinfunction "12_12") (pintype "passive"))
    )
    (net (code "2") (name "B2") (class "Default")
      (node (ref "IC2") (pin "11") (pinfunction "B2_11") (pintype "bidirectional"))
      (node (ref "SD_CARD") (pin "10") (pinfunction "10_10") (pintype "passive"))
    )
    (net (code "3") (name "B3") (class "Default")
      (node (ref "IC2") (pin "10") (pinfunction "B3_10") (pintype "bidirectional"))
      (node (ref "SD_CARD") (pin "6") (pinfunction "6_6") (pintype "passive"))
    )
    (net (code "4") (name "B4") (class "Default")
      (node (ref "IC2") (pin "9") (pinfunction "B4_9") (pintype "bidirectional"))
      (node (ref "SD_CARD") (pin "8") (pinfunction "8_8") (pintype "passive"))
    )
    (net (code "5") (name "CHILDCLOCK") (class "Default")
      (node (ref "J5") (pin "5") (pinfunction "5_5") (pintype "bidirectional"))
      (node (ref "SOCKET_2") (pin "5") (pinfunction "5_5") (pintype "passive"))
    )
    (net (code "6") (name "CHILDCLOCK_GPIO") (class "Default")
      (node (ref "JP21") (pin "2") (pinfunction "2_2") (pintype "passive"))
    )
    (net (code "7") (name "CHILDRESET") (class "Default")
      (node (ref "JP24") (pin "2") (pinfunction "2_2") (pintype "passive"))
      (node (ref "JP24") (pin "4") (pinfunction "4_4") (pintype "passive"))
      (node (ref "SOCKET_2") (pin "6") (pinfunction "6_6") (pintype "passive"))
    )
    (net (code "8") (name "CHILDRESET_GPIO") (class "Default")
      (node (ref "JP18") (pin "5") (pinfunction "5_5") (pintype "passive"))
      (node (ref "JP24") (pin "1") (pinfunction "1_1") (pintype "passive"))
    )
    (net (code "9") (name "CLOCK_GPIO") (class "Default")
      (node (ref "JP21") (pin "4") (pinfunction "4_4") (pintype "passive"))
    )
    (net (code "10") (name "FLASH_CS") (class "Default")
      (node (ref "FLASH") (pin "12") (pinfunction "12_12") (pintype "passive"))
      (node (ref "IC1") (pin "12") (pinfunction "B1_12") (pintype "bidirectional"))
    )
    (net (code "11") (name "FLASH_MISO") (class "Default")
      (node (ref "FLASH") (pin "8") (pinfunction "8_8") (pintype "passive"))
      (node (ref "IC1") (pin "11") (pinfunction "B2_11") (pintype "bidirectional"))
    )
    (net (code "12") (name "FLASH_MOSI") (class "Default")
      (node (ref "FLASH") (pin "10") (pinfunction "10_10") (pintype "passive"))
      (node (ref "IC1") (pin "10") (pinfunction "B3_10") (pintype "bidirectional"))
    )
    (net (code "13") (name "FLASH_SCK") (class "Default")
      (node (ref "FLASH") (pin "6") (pinfunction "6_6") (pintype "passive"))
      (node (ref "IC1") (pin "9") (pinfunction "B4_9") (pintype "bidirectional"))
    )
    (net (code "14") (name "GND") (class "Default")
      (node (ref "C1") (pin "2") (pinfunction "2_2") (pintype "passive"))
      (node (ref "C13") (pin "2") (pinfunction "2_2") (pintype "passive"))
      (node (ref "C14") (pin "2") (pinfunction "2_2") (pintype "passive"))
      (node (ref "C15") (pin "2") (pinfunction "2_2") (pintype "passive"))
      (node (ref "C16") (pin "2") (pinfunction "2_2") (pintype "passive"))
      (node (ref "C17") (pin "2") (pinfunction "2_2") (pintype "passive"))
      (node (ref "C18") (pin "2") (pinfunction "2_2") (pintype "passive"))
      (node (ref "C19") (pin "2") (pinfunction "2_2") (pintype "passive"))
      (node (ref "C2") (pin "2") (pinfunction "2_2") (pintype "passive"))
      (node (ref "C20") (pin "2") (pinfunction "2_2") (pintype "passive"))
      (node (ref "C21") (pin "2") (pinfunction "2_2") (pintype "passive"))
      (node (ref "C22") (pin "2") (pinfunction "2_2") (pintype "passive"))
      (node (ref "C3") (pin "2") (pinfunction "2_2") (pintype "passive"))
      (node (ref "C4") (pin "2") (pinfunction "2_2") (pintype "passive"))
      (node (ref "C5") (pin "2") (pinfunction "2_2") (pintype "passive"))
      (node (ref "C6") (pin "2") (pinfunction "2_2") (pintype "passive"))
      (node (ref "D4") (pin "C") (pinfunction "C_C") (pintype "passive"))
      (node (ref "FLASH") (pin "3") (pinfunction "3_3") (pintype "passive"))
      (node (ref "FLASH") (pin "4") (pinfunction "4_4") (pintype "passive"))
      (node (ref "GND") (pin "1") (pinfunction "1_1") (pintype "passive"))
      (node (ref "GND") (pin "2") (pinfunction "2_2") (pintype "passive"))
      (node (ref "GND") (pin "3") (pinfunction "3_3") (pintype "passive"))
      (node (ref "GND") (pin "4") (pinfunction "4_4") (pintype "passive"))
      (node (ref "GND") (pin "5") (pinfunction "5_5") (pintype "passive"))
      (node (ref "GND") (pin "6") (pinfunction "6_6") (pintype "passive"))
      (node (ref "IC1") (pin "16") (pinfunction "DIR2_16") (pintype "bidirectional"))
      (node (ref "IC1") (pin "8") (pinfunction "GND_8") (pintype "bidirectional"))
      (node (ref "IC2") (pin "6") (pinfunction "DIR4_6") (pintype "bidirectional"))
      (node (ref "IC2") (pin "8") (pinfunction "GND_8") (pintype "bidirectional"))
      (node (ref "IC3") (pin "15") (pinfunction "DIR1_15") (pintype "bidirectional"))
      (node (ref "IC3") (pin "16") (pinfunction "DIR2_16") (pintype "bidirectional"))
      (node (ref "IC3") (pin "5") (pinfunction "DIR3_5") (pintype "bidirectional"))
      (node (ref "IC3") (pin "8") (pinfunction "GND_8") (pintype "bidirectional"))
      (node (ref "IC7") (pin "1") (pinfunction "ADJ/GND_1") (pintype "bidirectional"))
      (node (ref "IC8") (pin "1") (pinfunction "ADJ/GND_1") (pintype "bidirectional"))
      (node (ref "IC9") (pin "1") (pinfunction "ADJ/GND_1") (pintype "bidirectional"))
      (node (ref "J4") (pin "1") (pinfunction "1_1") (pintype "bidirectional"))
      (node (ref "J4") (pin "2") (pinfunction "2_2") (pintype "bidirectional"))
      (node (ref "J4") (pin "3") (pinfunction "3_3") (pintype "bidirectional"))
      (node (ref "J4") (pin "4") (pinfunction "4_4") (pintype "bidirectional"))
      (node (ref "J5") (pin "1") (pinfunction "1_1") (pintype "bidirectional"))
      (node (ref "J5") (pin "2") (pinfunction "2_2") (pintype "bidirectional"))
      (node (ref "J5") (pin "3") (pinfunction "3_3") (pintype "bidirectional"))
      (node (ref "J5") (pin "4") (pinfunction "4_4") (pintype "bidirectional"))
      (node (ref "JP18") (pin "12") (pinfunction "12_12") (pintype "passive"))
      (node (ref "JP18") (pin "30") (pinfunction "30_30") (pintype "passive"))
      (node (ref "JP19") (pin "12") (pinfunction "12_12") (pintype "passive"))
      (node (ref "JP19") (pin "30") (pinfunction "30_30") (pintype "passive"))
      (node (ref "JP20") (pin "12") (pinfunction "12_12") (pintype "passive"))
      (node (ref "JP20") (pin "30") (pinfunction "30_30") (pintype "passive"))
      (node (ref "JP21") (pin "12") (pinfunction "12_12") (pintype "passive"))
      (node (ref "JP21") (pin "30") (pinfunction "30_30") (pintype "passive"))
      (node (ref "JTAG_20_PIN") (pin "10") (pinfunction "10_10") (pintype "passive"))
      (node (ref "JTAG_20_PIN") (pin "12") (pinfunction "12_12") (pintype "passive"))
      (node (ref "JTAG_20_PIN") (pin "14") (pinfunction "14_14") (pintype "passive"))
      (node (ref "JTAG_20_PIN") (pin "16") (pinfunction "16_16") (pintype "passive"))
      (node (ref "JTAG_20_PIN") (pin "18") (pinfunction "18_18") (pintype "passive"))
      (node (ref "JTAG_20_PIN") (pin "20") (pinfunction "20_20") (pintype "passive"))
      (node (ref "JTAG_20_PIN") (pin "4") (pinfunction "4_4") (pintype "passive"))
      (node (ref "JTAG_20_PIN") (pin "6") (pinfunction "6_6") (pintype "passive"))
      (node (ref "JTAG_20_PIN") (pin "8") (pinfunction "8_8") (pintype "passive"))
      (node (ref "Q10") (pin "2") (pinfunction "S_2") (pintype "bidirectional"))
      (node (ref "Q11") (pin "2") (pinfunction "S_2") (pintype "bidirectional"))
      (node (ref "Q12") (pin "2") (pinfunction "S_2") (pintype "bidirectional"))
      (node (ref "Q13") (pin "2") (pinfunction "S_2") (pintype "bidirectional"))
      (node (ref "Q3") (pin "2") (pinfunction "S_2") (pintype "bidirectional"))
      (node (ref "Q4") (pin "2") (pinfunction "S_2") (pintype "bidirectional"))
      (node (ref "Q5") (pin "2") (pinfunction "S_2") (pintype "bidirectional"))
      (node (ref "Q6") (pin "2") (pinfunction "S_2") (pintype "bidirectional"))
      (node (ref "Q7") (pin "2") (pinfunction "S_2") (pintype "bidirectional"))
      (node (ref "Q8") (pin "2") (pinfunction "S_2") (pintype "bidirectional"))
      (node (ref "Q9") (pin "2") (pinfunction "S_2") (pintype "bidirectional"))
      (node (ref "R1") (pin "1") (pinfunction "1_1") (pintype "passive"))
      (node (ref "R2") (pin "1") (pinfunction "1_1") (pintype "passive"))
      (node (ref "R2") (pin "2") (pinfunction "2_2") (pintype "passive"))
      (node (ref "R3") (pin "1") (pinfunction "1_1") (pintype "passive"))
      (node (ref "R4") (pin "1") (pinfunction "1_1") (pintype "passive"))
      (node (ref "R4") (pin "2") (pinfunction "2_2") (pintype "passive"))
      (node (ref "R5") (pin "1") (pinfunction "1_1") (pintype "passive"))
      (node (ref "R6") (pin "1") (pinfunction "1_1") (pintype "passive"))
      (node (ref "R6") (pin "2") (pinfunction "2_2") (pintype "passive"))
      (node (ref "R61") (pin "1") (pinfunction "1_1") (pintype "passive"))
      (node (ref "R62") (pin "1") (pinfunction "1_1") (pintype "passive"))
      (node (ref "R63") (pin "1") (pinfunction "1_1") (pintype "passive"))
      (node (ref "R64") (pin "1") (pinfunction "1_1") (pintype "passive"))
      (node (ref "R65") (pin "1") (pinfunction "1_1") (pintype "passive"))
      (node (ref "R66") (pin "1") (pinfunction "1_1") (pintype "passive"))
      (node (ref "R67") (pin "1") (pinfunction "1_1") (pintype "passive"))
      (node (ref "R68") (pin "1") (pinfunction "1_1") (pintype "passive"))
      (node (ref "R69") (pin "1") (pinfunction "1_1") (pintype "passive"))
      (node (ref "R7") (pin "1") (pinfunction "1_1") (pintype "passive"))
      (node (ref "R70") (pin "1") (pinfunction "1_1") (pintype "passive"))
      (node (ref "R71") (pin "1") (pinfunction "1_1") (pintype "passive"))
      (node (ref "R8") (pin "1") (pinfunction "1_1") (pintype "passive"))
      (node (ref "R9") (pin "1") (pinfunction "1_1") (pintype "passive"))
      (node (ref "S1") (pin "1") (pinfunction "1_1") (pintype "bidirectional"))
      (node (ref "S1") (pin "2") (pinfunction "2_2") (pintype "bidirectional"))
      (node (ref "S1") (pin "3") (pinfunction "3_3") (pintype "bidirectional"))
      (node (ref "S1_DIP8") (pin "10") (pinfunction "10_10") (pintype "bidirectional"))
      (node (ref "S1_DIP8") (pin "11") (pinfunction "11_11") (pintype "bidirectional"))
      (node (ref "S1_DIP8") (pin "12") (pinfunction "12_12") (pintype "bidirectional"))
      (node (ref "S1_DIP8") (pin "13") (pinfunction "13_13") (pintype "bidirectional"))
      (node (ref "S1_DIP8") (pin "14") (pinfunction "14_14") (pintype "bidirectional"))
      (node (ref "S1_DIP8") (pin "15") (pinfunction "15_15") (pintype "bidirectional"))
      (node (ref "S1_DIP8") (pin "16") (pinfunction "16_16") (pintype "bidirectional"))
      (node (ref "S1_DIP8") (pin "9") (pinfunction "9_9") (pintype "bidirectional"))
      (node (ref "SD_CARD") (pin "3") (pinfunction "3_3") (pintype "passive"))
      (node (ref "SD_CARD") (pin "4") (pinfunction "4_4") (pintype "passive"))
      (node (ref "SOCKET_1") (pin "11") (pinfunction "11_11") (pintype "passive"))
      (node (ref "SOCKET_1") (pin "30") (pinfunction "30_30") (pintype "passive"))
      (node (ref "SOCKET_2") (pin "22") (pinfunction "22_22") (pintype "passive"))
      (node (ref "SOCKET_2") (pin "8") (pinfunction "8_8") (pintype "passive"))
      (node (ref "SOCKET_3") (pin "11") (pinfunction "11_11") (pintype "passive"))
      (node (ref "SOCKET_3") (pin "30") (pinfunction "30_30") (pintype "passive"))
      (node (ref "SOCKET_4") (pin "22") (pinfunction "22_22") (pintype "passive"))
      (node (ref "SOCKET_4") (pin "8") (pinfunction "8_8") (pintype "passive"))
      (node (ref "SOCKET_5") (pin "11") (pinfunction "11_11") (pintype "passive"))
      (node (ref "SOCKET_5") (pin "30") (pinfunction "30_30") (pintype "passive"))
      (node (ref "SOCKET_6") (pin "22") (pinfunction "22_22") (pintype "passive"))
      (node (ref "SOCKET_6") (pin "8") (pinfunction "8_8") (pintype "passive"))
      (node (ref "SOCKET_7") (pin "11") (pinfunction "11_11") (pintype "passive"))
      (node (ref "SOCKET_7") (pin "30") (pinfunction "30_30") (pintype "passive"))
      (node (ref "SOCKET_8") (pin "22") (pinfunction "22_22") (pintype "passive"))
      (node (ref "SOCKET_8") (pin "8") (pinfunction "8_8") (pintype "passive"))
      (node (ref "USB-UART") (pin "1") (pinfunction "1_1") (pintype "passive"))
    )
    (net (code "15") (name "GPIO_IN[0]") (class "Default")
      (node (ref "JP4") (pin "1") (pinfunction "1_1") (pintype "passive"))
      (node (ref "SOCKET_1") (pin "15") (pinfunction "15_15") (pintype "passive"))
    )
    (net (code "16") (name "GPIO_IN[1]") (class "Default")
      (node (ref "JP4") (pin "3") (pinfunction "3_3") (pintype "passive"))
      (node (ref "SOCKET_1") (pin "14") (pinfunction "14_14") (pintype "passive"))
    )
    (net (code "17") (name "GPIO_IN[2]") (class "Default")
      (node (ref "JP4") (pin "5") (pinfunction "5_5") (pintype "passive"))
      (node (ref "SOCKET_1") (pin "13") (pinfunction "13_13") (pintype "passive"))
    )
    (net (code "18") (name "GPIO_IN[3]") (class "Default")
      (node (ref "JP4") (pin "7") (pinfunction "7_7") (pintype "passive"))
      (node (ref "SOCKET_1") (pin "12") (pinfunction "12_12") (pintype "passive"))
    )
    (net (code "19") (name "GPIO_IN[4]") (class "Default")
      (node (ref "JP4") (pin "9") (pinfunction "9_9") (pintype "passive"))
      (node (ref "SOCKET_1") (pin "10") (pinfunction "10_10") (pintype "passive"))
    )
    (net (code "20") (name "GPIO_IN[5]") (class "Default")
      (node (ref "JP4") (pin "11") (pinfunction "11_11") (pintype "passive"))
      (node (ref "SOCKET_1") (pin "9") (pinfunction "9_9") (pintype "passive"))
    )
    (net (code "21") (name "GPIO_IN[6]") (class "Default")
      (node (ref "JP4") (pin "13") (pinfunction "13_13") (pintype "passive"))
      (node (ref "SOCKET_1") (pin "8") (pinfunction "8_8") (pintype "passive"))
    )
    (net (code "22") (name "GPIO_IN[7]") (class "Default")
      (node (ref "JP4") (pin "15") (pinfunction "15_15") (pintype "passive"))
      (node (ref "SOCKET_1") (pin "7") (pinfunction "7_7") (pintype "passive"))
    )
    (net (code "23") (name "GPIO_OUT[0]") (class "Default")
      (node (ref "JP10") (pin "1") (pinfunction "1_1") (pintype "passive"))
      (node (ref "SOCKET_1") (pin "25") (pinfunction "25_25") (pintype "passive"))
    )
    (net (code "24") (name "GPIO_OUT[1]") (class "Default")
      (node (ref "JP10") (pin "3") (pinfunction "3_3") (pintype "passive"))
      (node (ref "SOCKET_1") (pin "23") (pinfunction "23_23") (pintype "passive"))
    )
    (net (code "25") (name "GPIO_OUT[2]") (class "Default")
      (node (ref "JP10") (pin "5") (pinfunction "5_5") (pintype "passive"))
      (node (ref "SOCKET_1") (pin "22") (pinfunction "22_22") (pintype "passive"))
    )
    (net (code "26") (name "GPIO_OUT[3]") (class "Default")
      (node (ref "JP10") (pin "7") (pinfunction "7_7") (pintype "passive"))
      (node (ref "SOCKET_1") (pin "21") (pinfunction "21_21") (pintype "passive"))
    )
    (net (code "27") (name "GPIO_OUT[4]") (class "Default")
      (node (ref "JP10") (pin "9") (pinfunction "9_9") (pintype "passive"))
      (node (ref "SOCKET_1") (pin "20") (pinfunction "20_20") (pintype "passive"))
    )
    (net (code "28") (name "GPIO_OUT[5]") (class "Default")
      (node (ref "JP10") (pin "11") (pinfunction "11_11") (pintype "passive"))
      (node (ref "SOCKET_1") (pin "19") (pinfunction "19_19") (pintype "passive"))
    )
    (net (code "29") (name "GPIO_OUT[6]") (class "Default")
      (node (ref "JP10") (pin "13") (pinfunction "13_13") (pintype "passive"))
      (node (ref "SOCKET_1") (pin "18") (pinfunction "18_18") (pintype "passive"))
    )
    (net (code "30") (name "GPIO_OUT[7]") (class "Default")
      (node (ref "JP10") (pin "15") (pinfunction "15_15") (pintype "passive"))
      (node (ref "SOCKET_1") (pin "17") (pinfunction "17_17") (pintype "passive"))
    )
    (net (code "31") (name "JRST_N") (class "Default")
      (node (ref "JP6") (pin "2") (pinfunction "2_2") (pintype "passive"))
      (node (ref "JP6") (pin "4") (pinfunction "4_4") (pintype "passive"))
      (node (ref "SOCKET_2") (pin "17") (pinfunction "17_17") (pintype "passive"))
    )
    (net (code "32") (name "JRST_N_GPIO") (class "Default")
      (node (ref "JP18") (pin "6") (pinfunction "6_6") (pintype "passive"))
      (node (ref "JP6") (pin "3") (pinfunction "3_3") (pintype "passive"))
    )
    (net (code "33") (name "JTAG_TCK") (class "Default")
      (node (ref "JP3") (pin "5") (pinfunction "5_5") (pintype "passive"))
      (node (ref "SOCKET_1") (pin "28") (pinfunction "28_28") (pintype "passive"))
    )
    (net (code "34") (name "JTAG_TDI") (class "Default")
      (node (ref "JP3") (pin "1") (pinfunction "1_1") (pintype "passive"))
      (node (ref "SOCKET_1") (pin "26") (pinfunction "26_26") (pintype "passive"))
    )
    (net (code "35") (name "JTAG_TDO") (class "Default")
      (node (ref "JP3") (pin "7") (pinfunction "7_7") (pintype "passive"))
      (node (ref "SOCKET_1") (pin "27") (pinfunction "27_27") (pintype "passive"))
    )
    (net (code "36") (name "JTAG_TMS") (class "Default")
      (node (ref "JP3") (pin "3") (pinfunction "3_3") (pintype "passive"))
      (node (ref "SOCKET_1") (pin "29") (pinfunction "29_29") (pintype "passive"))
    )
    (net (code "37") (name "LED_0") (class "Default")
      (node (ref "JP10") (pin "2") (pinfunction "2_2") (pintype "passive"))
      (node (ref "Q6") (pin "1") (pinfunction "G_1") (pintype "bidirectional"))
      (node (ref "R64") (pin "2") (pinfunction "2_2") (pintype "passive"))
    )
    (net (code "38") (name "LED_1") (class "Default")
      (node (ref "JP10") (pin "4") (pinfunction "4_4") (pintype "passive"))
      (node (ref "Q7") (pin "1") (pinfunction "G_1") (pintype "bidirectional"))
      (node (ref "R65") (pin "2") (pinfunction "2_2") (pintype "passive"))
    )
    (net (code "39") (name "LED_2") (class "Default")
      (node (ref "JP10") (pin "6") (pinfunction "6_6") (pintype "passive"))
      (node (ref "Q8") (pin "1") (pinfunction "G_1") (pintype "bidirectional"))
      (node (ref "R66") (pin "2") (pinfunction "2_2") (pintype "passive"))
    )
    (net (code "40") (name "LED_3") (class "Default")
      (node (ref "JP10") (pin "8") (pinfunction "8_8") (pintype "passive"))
      (node (ref "Q9") (pin "1") (pinfunction "G_1") (pintype "bidirectional"))
      (node (ref "R67") (pin "2") (pinfunction "2_2") (pintype "passive"))
    )
    (net (code "41") (name "LED_4") (class "Default")
      (node (ref "JP10") (pin "10") (pinfunction "10_10") (pintype "passive"))
      (node (ref "Q10") (pin "1") (pinfunction "G_1") (pintype "bidirectional"))
      (node (ref "R68") (pin "2") (pinfunction "2_2") (pintype "passive"))
    )
    (net (code "42") (name "LED_5") (class "Default")
      (node (ref "JP10") (pin "12") (pinfunction "12_12") (pintype "passive"))
      (node (ref "Q11") (pin "1") (pinfunction "G_1") (pintype "bidirectional"))
      (node (ref "R69") (pin "2") (pinfunction "2_2") (pintype "passive"))
    )
    (net (code "43") (name "LED_6") (class "Default")
      (node (ref "JP10") (pin "14") (pinfunction "14_14") (pintype "passive"))
      (node (ref "Q12") (pin "1") (pinfunction "G_1") (pintype "bidirectional"))
      (node (ref "R70") (pin "2") (pinfunction "2_2") (pintype "passive"))
    )
    (net (code "44") (name "LED_7") (class "Default")
      (node (ref "JP10") (pin "16") (pinfunction "16_16") (pintype "passive"))
      (node (ref "Q13") (pin "1") (pinfunction "G_1") (pintype "bidirectional"))
      (node (ref "R71") (pin "2") (pinfunction "2_2") (pintype "passive"))
    )
    (net (code "45") (name "Net-(D4-PadA)") (class "Default")
      (node (ref "D4") (pin "A") (pinfunction "A_A") (pintype "passive"))
      (node (ref "R46") (pin "1") (pinfunction "1_1") (pintype "passive"))
    )
    (net (code "46") (name "Net-(D5-PadA)") (class "Default")
      (node (ref "D5") (pin "A") (pinfunction "A_A") (pintype "passive"))
      (node (ref "R48") (pin "1") (pinfunction "1_1") (pintype "passive"))
    )
    (net (code "47") (name "Net-(D6-PadA)") (class "Default")
      (node (ref "D6") (pin "A") (pinfunction "A_A") (pintype "passive"))
      (node (ref "R49") (pin "1") (pinfunction "1_1") (pintype "passive"))
    )
    (net (code "48") (name "Net-(D7-PadA)") (class "Default")
      (node (ref "D7") (pin "A") (pinfunction "A_A") (pintype "passive"))
      (node (ref "R50") (pin "1") (pinfunction "1_1") (pintype "passive"))
    )
    (net (code "49") (name "Net-(D8-PadA)") (class "Default")
      (node (ref "D8") (pin "A") (pinfunction "A_A") (pintype "passive"))
      (node (ref "R51") (pin "1") (pinfunction "1_1") (pintype "passive"))
    )
    (net (code "50") (name "Net-(D9-PadA)") (class "Default")
      (node (ref "D9") (pin "A") (pinfunction "A_A") (pintype "passive"))
      (node (ref "R52") (pin "1") (pinfunction "1_1") (pintype "passive"))
    )
    (net (code "51") (name "Net-(D10-PadA)") (class "Default")
      (node (ref "D10") (pin "A") (pinfunction "A_A") (pintype "passive"))
      (node (ref "R47") (pin "1") (pinfunction "1_1") (pintype "passive"))
    )
    (net (code "52") (name "Net-(D11-PadA)") (class "Default")
      (node (ref "D11") (pin "A") (pinfunction "A_A") (pintype "passive"))
      (node (ref "R53") (pin "1") (pinfunction "1_1") (pintype "passive"))
    )
    (net (code "53") (name "Net-(D12-PadA)") (class "Default")
      (node (ref "D12") (pin "A") (pinfunction "A_A") (pintype "passive"))
      (node (ref "R54") (pin "1") (pinfunction "1_1") (pintype "passive"))
    )
    (net (code "54") (name "Net-(D13-PadA)") (class "Default")
      (node (ref "D13") (pin "A") (pinfunction "A_A") (pintype "passive"))
      (node (ref "R55") (pin "1") (pinfunction "1_1") (pintype "passive"))
    )
    (net (code "55") (name "Net-(D14-PadA)") (class "Default")
      (node (ref "D14") (pin "A") (pinfunction "A_A") (pintype "passive"))
      (node (ref "R56") (pin "1") (pinfunction "1_1") (pintype "passive"))
    )
    (net (code "56") (name "Net-(D15-PadA)") (class "Default")
      (node (ref "D15") (pin "A") (pinfunction "A_A") (pintype "passive"))
      (node (ref "R57") (pin "1") (pinfunction "1_1") (pintype "passive"))
    )
    (net (code "57") (name "Net-(IC1-A1)") (class "Default")
      (node (ref "IC1") (pin "1") (pinfunction "A1_1") (pintype "bidirectional"))
      (node (ref "JP2") (pin "2") (pinfunction "2_2") (pintype "passive"))
    )
    (net (code "58") (name "Net-(IC1-A2)") (class "Default")
      (node (ref "IC1") (pin "2") (pinfunction "A2_2") (pintype "bidirectional"))
      (node (ref "JP2") (pin "4") (pinfunction "4_4") (pintype "passive"))
    )
    (net (code "59") (name "Net-(IC1-A3)") (class "Default")
      (node (ref "IC1") (pin "3") (pinfunction "A3_3") (pintype "bidirectional"))
      (node (ref "JP2") (pin "6") (pinfunction "6_6") (pintype "passive"))
    )
    (net (code "60") (name "Net-(IC1-A4)") (class "Default")
      (node (ref "IC1") (pin "4") (pinfunction "A4_4") (pintype "bidirectional"))
      (node (ref "JP2") (pin "8") (pinfunction "8_8") (pintype "passive"))
    )
    (net (code "61") (name "Net-(IC1-~{OE})") (class "Default")
      (node (ref "IC1") (pin "7") (pinfunction "~{OE}_7") (pintype "bidirectional"))
      (node (ref "R8") (pin "2") (pinfunction "2_2") (pintype "passive"))
    )
    (net (code "62") (name "Net-(IC2-A1)") (class "Default")
      (node (ref "IC2") (pin "1") (pinfunction "A1_1") (pintype "bidirectional"))
      (node (ref "JP1") (pin "2") (pinfunction "2_2") (pintype "passive"))
    )
    (net (code "63") (name "Net-(IC2-A2)") (class "Default")
      (node (ref "IC2") (pin "2") (pinfunction "A2_2") (pintype "bidirectional"))
      (node (ref "JP1") (pin "4") (pinfunction "4_4") (pintype "passive"))
    )
    (net (code "64") (name "Net-(IC2-A3)") (class "Default")
      (node (ref "IC2") (pin "3") (pinfunction "A3_3") (pintype "bidirectional"))
      (node (ref "JP1") (pin "6") (pinfunction "6_6") (pintype "passive"))
    )
    (net (code "65") (name "Net-(IC2-A4)") (class "Default")
      (node (ref "IC2") (pin "4") (pinfunction "A4_4") (pintype "bidirectional"))
      (node (ref "JP1") (pin "8") (pinfunction "8_8") (pintype "passive"))
    )
    (net (code "66") (name "Net-(IC2-~{OE})") (class "Default")
      (node (ref "IC2") (pin "7") (pinfunction "~{OE}_7") (pintype "bidirectional"))
      (node (ref "R7") (pin "2") (pinfunction "2_2") (pintype "passive"))
    )
    (net (code "67") (name "Net-(IC3-A1)") (class "Default")
      (node (ref "IC3") (pin "1") (pinfunction "A1_1") (pintype "bidirectional"))
      (node (ref "JP3") (pin "2") (pinfunction "2_2") (pintype "passive"))
    )
    (net (code "68") (name "Net-(IC3-A2)") (class "Default")
      (node (ref "IC3") (pin "2") (pinfunction "A2_2") (pintype "bidirectional"))
      (node (ref "JP3") (pin "4") (pinfunction "4_4") (pintype "passive"))
    )
    (net (code "69") (name "Net-(IC3-A3)") (class "Default")
      (node (ref "IC3") (pin "3") (pinfunction "A3_3") (pintype "bidirectional"))
      (node (ref "JP3") (pin "6") (pinfunction "6_6") (pintype "passive"))
    )
    (net (code "70") (name "Net-(IC3-A4)") (class "Default")
      (node (ref "IC3") (pin "4") (pinfunction "A4_4") (pintype "bidirectional"))
      (node (ref "JP3") (pin "8") (pinfunction "8_8") (pintype "passive"))
    )
    (net (code "71") (name "Net-(IC3-~{OE})") (class "Default")
      (node (ref "IC3") (pin "7") (pinfunction "~{OE}_7") (pintype "bidirectional"))
      (node (ref "R9") (pin "2") (pinfunction "2_2") (pintype "passive"))
    )
    (net (code "72") (name "Net-(JP4-Pad2)") (class "Default")
      (node (ref "JP4") (pin "2") (pinfunction "2_2") (pintype "passive"))
      (node (ref "R33") (pin "1") (pinfunction "1_1") (pintype "passive"))
      (node (ref "S1_DIP8") (pin "1") (pinfunction "1_1") (pintype "bidirectional"))
    )
    (net (code "73") (name "Net-(JP4-Pad4)") (class "Default")
      (node (ref "JP4") (pin "4") (pinfunction "4_4") (pintype "passive"))
      (node (ref "R32") (pin "1") (pinfunction "1_1") (pintype "passive"))
      (node (ref "S1_DIP8") (pin "2") (pinfunction "2_2") (pintype "bidirectional"))
    )
    (net (code "74") (name "Net-(JP4-Pad6)") (class "Default")
      (node (ref "JP4") (pin "6") (pinfunction "6_6") (pintype "passive"))
      (node (ref "R31") (pin "1") (pinfunction "1_1") (pintype "passive"))
      (node (ref "S1_DIP8") (pin "3") (pinfunction "3_3") (pintype "bidirectional"))
    )
    (net (code "75") (name "Net-(JP4-Pad8)") (class "Default")
      (node (ref "JP4") (pin "8") (pinfunction "8_8") (pintype "passive"))
      (node (ref "R30") (pin "1") (pinfunction "1_1") (pintype "passive"))
      (node (ref "S1_DIP8") (pin "4") (pinfunction "4_4") (pintype "bidirectional"))
    )
    (net (code "76") (name "Net-(JP4-Pad10)") (class "Default")
      (node (ref "JP4") (pin "10") (pinfunction "10_10") (pintype "passive"))
      (node (ref "R29") (pin "1") (pinfunction "1_1") (pintype "passive"))
      (node (ref "S1_DIP8") (pin "5") (pinfunction "5_5") (pintype "bidirectional"))
    )
    (net (code "77") (name "Net-(JP4-Pad12)") (class "Default")
      (node (ref "JP4") (pin "12") (pinfunction "12_12") (pintype "passive"))
      (node (ref "R28") (pin "1") (pinfunction "1_1") (pintype "passive"))
      (node (ref "S1_DIP8") (pin "6") (pinfunction "6_6") (pintype "bidirectional"))
    )
    (net (code "78") (name "Net-(JP4-Pad14)") (class "Default")
      (node (ref "JP4") (pin "14") (pinfunction "14_14") (pintype "passive"))
      (node (ref "R27") (pin "1") (pinfunction "1_1") (pintype "passive"))
      (node (ref "S1_DIP8") (pin "7") (pinfunction "7_7") (pintype "bidirectional"))
    )
    (net (code "79") (name "Net-(JP4-Pad16)") (class "Default")
      (node (ref "JP4") (pin "16") (pinfunction "16_16") (pintype "passive"))
      (node (ref "R26") (pin "1") (pinfunction "1_1") (pintype "passive"))
      (node (ref "S1_DIP8") (pin "8") (pinfunction "8_8") (pintype "bidirectional"))
    )
    (net (code "80") (name "Net-(JP5-Pad3)") (class "Default")
      (node (ref "JP5") (pin "3") (pinfunction "3_3") (pintype "passive"))
      (node (ref "R59") (pin "1") (pinfunction "1_1") (pintype "passive"))
      (node (ref "S1") (pin "5") (pinfunction "5_5") (pintype "bidirectional"))
    )
    (net (code "81") (name "Net-(JP6-Pad1)") (class "Default")
      (node (ref "JP6") (pin "1") (pinfunction "1_1") (pintype "passive"))
      (node (ref "R58") (pin "1") (pinfunction "1_1") (pintype "passive"))
      (node (ref "S1") (pin "4") (pinfunction "4_4") (pintype "bidirectional"))
    )
    (net (code "82") (name "Net-(JP24-Pad3)") (class "Default")
      (node (ref "JP24") (pin "3") (pinfunction "3_3") (pintype "passive"))
      (node (ref "R60") (pin "1") (pinfunction "1_1") (pintype "passive"))
      (node (ref "S1") (pin "6") (pinfunction "6_6") (pintype "bidirectional"))
    )
    (net (code "83") (name "Net-(Q3-D)") (class "Default")
      (node (ref "D10") (pin "C") (pinfunction "C_C") (pintype "passive"))
      (node (ref "Q3") (pin "3") (pinfunction "D_3") (pintype "bidirectional"))
    )
    (net (code "84") (name "Net-(Q4-D)") (class "Default")
      (node (ref "D5") (pin "C") (pinfunction "C_C") (pintype "passive"))
      (node (ref "Q4") (pin "3") (pinfunction "D_3") (pintype "bidirectional"))
    )
    (net (code "85") (name "Net-(Q5-D)") (class "Default")
      (node (ref "D6") (pin "C") (pinfunction "C_C") (pintype "passive"))
      (node (ref "Q5") (pin "3") (pinfunction "D_3") (pintype "bidirectional"))
    )
    (net (code "86") (name "Net-(Q6-D)") (class "Default")
      (node (ref "D7") (pin "C") (pinfunction "C_C") (pintype "passive"))
      (node (ref "Q6") (pin "3") (pinfunction "D_3") (pintype "bidirectional"))
    )
    (net (code "87") (name "Net-(Q7-D)") (class "Default")
      (node (ref "D8") (pin "C") (pinfunction "C_C") (pintype "passive"))
      (node (ref "Q7") (pin "3") (pinfunction "D_3") (pintype "bidirectional"))
    )
    (net (code "88") (name "Net-(Q8-D)") (class "Default")
      (node (ref "D9") (pin "C") (pinfunction "C_C") (pintype "passive"))
      (node (ref "Q8") (pin "3") (pinfunction "D_3") (pintype "bidirectional"))
    )
    (net (code "89") (name "Net-(Q9-D)") (class "Default")
      (node (ref "D11") (pin "C") (pinfunction "C_C") (pintype "passive"))
      (node (ref "Q9") (pin "3") (pinfunction "D_3") (pintype "bidirectional"))
    )
    (net (code "90") (name "Net-(Q10-D)") (class "Default")
      (node (ref "D12") (pin "C") (pinfunction "C_C") (pintype "passive"))
      (node (ref "Q10") (pin "3") (pinfunction "D_3") (pintype "bidirectional"))
    )
    (net (code "91") (name "Net-(Q11-D)") (class "Default")
      (node (ref "D13") (pin "C") (pinfunction "C_C") (pintype "passive"))
      (node (ref "Q11") (pin "3") (pinfunction "D_3") (pintype "bidirectional"))
    )
    (net (code "92") (name "Net-(Q12-D)") (class "Default")
      (node (ref "D14") (pin "C") (pinfunction "C_C") (pintype "passive"))
      (node (ref "Q12") (pin "3") (pinfunction "D_3") (pintype "bidirectional"))
    )
    (net (code "93") (name "Net-(Q13-D)") (class "Default")
      (node (ref "D15") (pin "C") (pinfunction "C_C") (pintype "passive"))
      (node (ref "Q13") (pin "3") (pinfunction "D_3") (pintype "bidirectional"))
    )
    (net (code "94") (name "PARAM[0]_5X5") (class "Default")
      (node (ref "PARAM_0_SELECT") (pin "1") (pinfunction "1_1") (pintype "passive"))
      (node (ref "SOCKET_2") (pin "28") (pinfunction "28_28") (pintype "passive"))
    )
    (net (code "95") (name "PARAM[0]_5X7.5") (class "Default")
      (node (ref "PARAM_0_SELECT") (pin "3") (pinfunction "3_3") (pintype "passive"))
      (node (ref "SOCKET_2") (pin "27") (pinfunction "27_27") (pintype "passive"))
    )
    (net (code "96") (name "QSPI_CS") (class "Default")
      (node (ref "JP2") (pin "1") (pinfunction "1_1") (pintype "passive"))
      (node (ref "SOCKET_2") (pin "7") (pinfunction "7_7") (pintype "passive"))
    )
    (net (code "97") (name "QSPI_MISO") (class "Default")
      (node (ref "JP2") (pin "3") (pinfunction "3_3") (pintype "passive"))
      (node (ref "SOCKET_2") (pin "10") (pinfunction "10_10") (pintype "passive"))
    )
    (net (code "98") (name "QSPI_MOSI") (class "Default")
      (node (ref "JP2") (pin "5") (pinfunction "5_5") (pintype "passive"))
      (node (ref "SOCKET_2") (pin "11") (pinfunction "11_11") (pintype "passive"))
    )
    (net (code "99") (name "QSPI_SCK") (class "Default")
      (node (ref "JP2") (pin "7") (pinfunction "7_7") (pintype "passive"))
      (node (ref "SOCKET_2") (pin "9") (pinfunction "9_9") (pintype "passive"))
    )
    (net (code "100") (name "RST_N") (class "Default")
      (node (ref "JP5") (pin "2") (pinfunction "2_2") (pintype "passive"))
      (node (ref "JP5") (pin "4") (pinfunction "4_4") (pintype "passive"))
      (node (ref "SOCKET_2") (pin "15") (pinfunction "15_15") (pintype "passive"))
    )
    (net (code "101") (name "RST_N_GPIO") (class "Default")
      (node (ref "JP18") (pin "2") (pinfunction "2_2") (pintype "passive"))
      (node (ref "JP5") (pin "1") (pinfunction "1_1") (pintype "passive"))
    )
    (net (code "102") (name "SDIO_CLK") (class "Default")
      (node (ref "JP1") (pin "5") (pinfunction "5_5") (pintype "passive"))
      (node (ref "SOCKET_1") (pin "31") (pinfunction "31_31") (pintype "passive"))
    )
    (net (code "103") (name "SDIO_CMD") (class "Default")
      (node (ref "JP1") (pin "3") (pinfunction "3_3") (pintype "passive"))
      (node (ref "SOCKET_1") (pin "32") (pinfunction "32_32") (pintype "passive"))
    )
    (net (code "104") (name "SDIO_DAT_0") (class "Default")
      (node (ref "JP1") (pin "7") (pinfunction "7_7") (pintype "passive"))
      (node (ref "SOCKET_2") (pin "1") (pinfunction "1_1") (pintype "passive"))
    )
    (net (code "105") (name "SDIO_DAT_3") (class "Default")
      (node (ref "JP1") (pin "1") (pinfunction "1_1") (pintype "passive"))
      (node (ref "SOCKET_2") (pin "2") (pinfunction "2_2") (pintype "passive"))
    )
    (net (code "106") (name "SYS_CLK") (class "Default")
      (node (ref "J4") (pin "5") (pinfunction "5_5") (pintype "bidirectional"))
      (node (ref "SOCKET_2") (pin "14") (pinfunction "14_14") (pintype "passive"))
    )
    (net (code "107") (name "TCK") (class "Default")
      (node (ref "IC3") (pin "10") (pinfunction "B3_10") (pintype "bidirectional"))
      (node (ref "JTAG_20_PIN") (pin "9") (pinfunction "9_9") (pintype "passive"))
      (node (ref "R24") (pin "1") (pinfunction "1_1") (pintype "passive"))
    )
    (net (code "108") (name "TDI") (class "Default")
      (node (ref "IC3") (pin "12") (pinfunction "B1_12") (pintype "bidirectional"))
      (node (ref "JTAG_20_PIN") (pin "5") (pinfunction "5_5") (pintype "passive"))
      (node (ref "R23") (pin "1") (pinfunction "1_1") (pintype "passive"))
    )
    (net (code "109") (name "TDO") (class "Default")
      (node (ref "IC3") (pin "9") (pinfunction "B4_9") (pintype "bidirectional"))
      (node (ref "JTAG_20_PIN") (pin "13") (pinfunction "13_13") (pintype "passive"))
      (node (ref "R25") (pin "1") (pinfunction "1_1") (pintype "passive"))
    )
    (net (code "110") (name "TLPORT_A_BITS_ADDRESS[0]") (class "Default")
      (node (ref "JP19") (pin "18") (pinfunction "18_18") (pintype "passive"))
      (node (ref "SOCKET_4") (pin "23") (pinfunction "23_23") (pintype "passive"))
    )
    (net (code "111") (name "TLPORT_A_BITS_ADDRESS[1]") (class "Default")
      (node (ref "JP19") (pin "17") (pinfunction "17_17") (pintype "passive"))
      (node (ref "SOCKET_4") (pin "21") (pinfunction "21_21") (pintype "passive"))
    )
    (net (code "112") (name "TLPORT_A_BITS_ADDRESS[2]") (class "Default")
      (node (ref "JP19") (pin "16") (pinfunction "16_16") (pintype "passive"))
      (node (ref "SOCKET_4") (pin "20") (pinfunction "20_20") (pintype "passive"))
    )
    (net (code "113") (name "TLPORT_A_BITS_ADDRESS[3]") (class "Default")
      (node (ref "JP19") (pin "15") (pinfunction "15_15") (pintype "passive"))
      (node (ref "SOCKET_4") (pin "18") (pinfunction "18_18") (pintype "passive"))
    )
    (net (code "114") (name "TLPORT_A_BITS_ADDRESS[4]") (class "Default")
      (node (ref "JP19") (pin "14") (pinfunction "14_14") (pintype "passive"))
      (node (ref "SOCKET_4") (pin "17") (pinfunction "17_17") (pintype "passive"))
    )
    (net (code "115") (name "TLPORT_A_BITS_ADDRESS[5]") (class "Default")
      (node (ref "JP19") (pin "13") (pinfunction "13_13") (pintype "passive"))
      (node (ref "SOCKET_4") (pin "15") (pinfunction "15_15") (pintype "passive"))
    )
    (net (code "116") (name "TLPORT_A_BITS_ADDRESS[6]") (class "Default")
      (node (ref "JP19") (pin "10") (pinfunction "10_10") (pintype "passive"))
      (node (ref "SOCKET_4") (pin "14") (pinfunction "14_14") (pintype "passive"))
    )
    (net (code "117") (name "TLPORT_A_BITS_ADDRESS[7]") (class "Default")
      (node (ref "JP19") (pin "9") (pinfunction "9_9") (pintype "passive"))
      (node (ref "SOCKET_4") (pin "13") (pinfunction "13_13") (pintype "passive"))
    )
    (net (code "118") (name "TLPORT_A_BITS_ADDRESS[8]") (class "Default")
      (node (ref "JP19") (pin "8") (pinfunction "8_8") (pintype "passive"))
      (node (ref "SOCKET_4") (pin "12") (pinfunction "12_12") (pintype "passive"))
    )
    (net (code "119") (name "TLPORT_A_BITS_ADDRESS[9]") (class "Default")
      (node (ref "JP19") (pin "7") (pinfunction "7_7") (pintype "passive"))
      (node (ref "SOCKET_4") (pin "11") (pinfunction "11_11") (pintype "passive"))
    )
    (net (code "120") (name "TLPORT_A_BITS_ADDRESS[10]") (class "Default")
      (node (ref "JP19") (pin "6") (pinfunction "6_6") (pintype "passive"))
      (node (ref "SOCKET_4") (pin "10") (pinfunction "10_10") (pintype "passive"))
    )
    (net (code "121") (name "TLPORT_A_BITS_ADDRESS[11]") (class "Default")
      (node (ref "JP19") (pin "5") (pinfunction "5_5") (pintype "passive"))
      (node (ref "SOCKET_4") (pin "9") (pinfunction "9_9") (pintype "passive"))
    )
    (net (code "122") (name "TLPORT_A_BITS_ADDRESS[12]") (class "Default")
      (node (ref "JP19") (pin "4") (pinfunction "4_4") (pintype "passive"))
      (node (ref "SOCKET_4") (pin "7") (pinfunction "7_7") (pintype "passive"))
    )
    (net (code "123") (name "TLPORT_A_BITS_ADDRESS[13]") (class "Default")
      (node (ref "JP19") (pin "3") (pinfunction "3_3") (pintype "passive"))
      (node (ref "SOCKET_4") (pin "6") (pinfunction "6_6") (pintype "passive"))
    )
    (net (code "124") (name "TLPORT_A_BITS_ADDRESS[14]") (class "Default")
      (node (ref "JP19") (pin "2") (pinfunction "2_2") (pintype "passive"))
      (node (ref "SOCKET_4") (pin "5") (pinfunction "5_5") (pintype "passive"))
    )
    (net (code "125") (name "TLPORT_A_BITS_ADDRESS[15]") (class "Default")
      (node (ref "JP19") (pin "1") (pinfunction "1_1") (pintype "passive"))
      (node (ref "SOCKET_4") (pin "4") (pinfunction "4_4") (pintype "passive"))
    )
    (net (code "126") (name "TLPORT_A_BITS_ADDRESS[16]") (class "Default")
      (node (ref "JP18") (pin "40") (pinfunction "40_40") (pintype "passive"))
      (node (ref "SOCKET_4") (pin "3") (pinfunction "3_3") (pintype "passive"))
    )
    (net (code "127") (name "TLPORT_A_BITS_ADDRESS[17]") (class "Default")
      (node (ref "JP18") (pin "39") (pinfunction "39_39") (pintype "passive"))
      (node (ref "SOCKET_4") (pin "2") (pinfunction "2_2") (pintype "passive"))
    )
    (net (code "128") (name "TLPORT_A_BITS_ADDRESS[18]") (class "Default")
      (node (ref "JP18") (pin "38") (pinfunction "38_38") (pintype "passive"))
      (node (ref "SOCKET_4") (pin "1") (pinfunction "1_1") (pintype "passive"))
    )
    (net (code "129") (name "TLPORT_A_BITS_ADDRESS[19]") (class "Default")
      (node (ref "JP18") (pin "37") (pinfunction "37_37") (pintype "passive"))
      (node (ref "SOCKET_3") (pin "32") (pinfunction "32_32") (pintype "passive"))
    )
    (net (code "130") (name "TLPORT_A_BITS_ADDRESS[20]") (class "Default")
      (node (ref "JP18") (pin "36") (pinfunction "36_36") (pintype "passive"))
      (node (ref "SOCKET_3") (pin "31") (pinfunction "31_31") (pintype "passive"))
    )
    (net (code "131") (name "TLPORT_A_BITS_ADDRESS[21]") (class "Default")
      (node (ref "JP18") (pin "35") (pinfunction "35_35") (pintype "passive"))
      (node (ref "SOCKET_3") (pin "29") (pinfunction "29_29") (pintype "passive"))
    )
    (net (code "132") (name "TLPORT_A_BITS_ADDRESS[22]") (class "Default")
      (node (ref "JP18") (pin "34") (pinfunction "34_34") (pintype "passive"))
      (node (ref "SOCKET_3") (pin "28") (pinfunction "28_28") (pintype "passive"))
    )
    (net (code "133") (name "TLPORT_A_BITS_ADDRESS[23]") (class "Default")
      (node (ref "JP18") (pin "33") (pinfunction "33_33") (pintype "passive"))
      (node (ref "SOCKET_3") (pin "27") (pinfunction "27_27") (pintype "passive"))
    )
    (net (code "134") (name "TLPORT_A_BITS_ADDRESS[24]") (class "Default")
      (node (ref "JP18") (pin "32") (pinfunction "32_32") (pintype "passive"))
      (node (ref "SOCKET_3") (pin "26") (pinfunction "26_26") (pintype "passive"))
    )
    (net (code "135") (name "TLPORT_A_BITS_ADDRESS[25]") (class "Default")
      (node (ref "JP18") (pin "31") (pinfunction "31_31") (pintype "passive"))
      (node (ref "SOCKET_3") (pin "25") (pinfunction "25_25") (pintype "passive"))
    )
    (net (code "136") (name "TLPORT_A_BITS_ADDRESS[26]") (class "Default")
      (node (ref "JP18") (pin "28") (pinfunction "28_28") (pintype "passive"))
      (node (ref "SOCKET_3") (pin "23") (pinfunction "23_23") (pintype "passive"))
    )
    (net (code "137") (name "TLPORT_A_BITS_ADDRESS[27]") (class "Default")
      (node (ref "JP18") (pin "27") (pinfunction "27_27") (pintype "passive"))
      (node (ref "SOCKET_3") (pin "22") (pinfunction "22_22") (pintype "passive"))
    )
    (net (code "138") (name "TLPORT_A_BITS_ADDRESS[28]") (class "Default")
      (node (ref "JP18") (pin "26") (pinfunction "26_26") (pintype "passive"))
      (node (ref "SOCKET_3") (pin "21") (pinfunction "21_21") (pintype "passive"))
    )
    (net (code "139") (name "TLPORT_A_BITS_ADDRESS[29]") (class "Default")
      (node (ref "JP18") (pin "25") (pinfunction "25_25") (pintype "passive"))
      (node (ref "SOCKET_3") (pin "20") (pinfunction "20_20") (pintype "passive"))
    )
    (net (code "140") (name "TLPORT_A_BITS_ADDRESS[30]") (class "Default")
      (node (ref "JP18") (pin "24") (pinfunction "24_24") (pintype "passive"))
      (node (ref "SOCKET_3") (pin "19") (pinfunction "19_19") (pintype "passive"))
    )
    (net (code "141") (name "TLPORT_A_BITS_ADDRESS[31]") (class "Default")
      (node (ref "JP18") (pin "23") (pinfunction "23_23") (pintype "passive"))
      (node (ref "SOCKET_3") (pin "18") (pinfunction "18_18") (pintype "passive"))
    )
    (net (code "142") (name "TLPORT_A_BITS_CORRUPT") (class "Default")
      (node (ref "JP20") (pin "19") (pinfunction "19_19") (pintype "passive"))
      (node (ref "SOCKET_6") (pin "14") (pinfunction "14_14") (pintype "passive"))
    )
    (net (code "143") (name "TLPORT_A_BITS_DATA[0]") (class "Default")
      (node (ref "JP20") (pin "18") (pinfunction "18_18") (pintype "passive"))
      (node (ref "SOCKET_6") (pin "13") (pinfunction "13_13") (pintype "passive"))
    )
    (net (code "144") (name "TLPORT_A_BITS_DATA[1]") (class "Default")
      (node (ref "JP20") (pin "17") (pinfunction "17_17") (pintype "passive"))
      (node (ref "SOCKET_6") (pin "12") (pinfunction "12_12") (pintype "passive"))
    )
    (net (code "145") (name "TLPORT_A_BITS_DATA[2]") (class "Default")
      (node (ref "JP20") (pin "16") (pinfunction "16_16") (pintype "passive"))
      (node (ref "SOCKET_6") (pin "11") (pinfunction "11_11") (pintype "passive"))
    )
    (net (code "146") (name "TLPORT_A_BITS_DATA[3]") (class "Default")
      (node (ref "JP20") (pin "15") (pinfunction "15_15") (pintype "passive"))
      (node (ref "SOCKET_6") (pin "10") (pinfunction "10_10") (pintype "passive"))
    )
    (net (code "147") (name "TLPORT_A_BITS_DATA[4]") (class "Default")
      (node (ref "JP20") (pin "14") (pinfunction "14_14") (pintype "passive"))
      (node (ref "SOCKET_6") (pin "9") (pinfunction "9_9") (pintype "passive"))
    )
    (net (code "148") (name "TLPORT_A_BITS_DATA[5]") (class "Default")
      (node (ref "JP20") (pin "13") (pinfunction "13_13") (pintype "passive"))
      (node (ref "SOCKET_6") (pin "7") (pinfunction "7_7") (pintype "passive"))
    )
    (net (code "149") (name "TLPORT_A_BITS_DATA[6]") (class "Default")
      (node (ref "JP20") (pin "1") (pinfunction "1_1") (pintype "passive"))
      (node (ref "SOCKET_6") (pin "6") (pinfunction "6_6") (pintype "passive"))
    )
    (net (code "150") (name "TLPORT_A_BITS_DATA[7]") (class "Default")
      (node (ref "JP20") (pin "2") (pinfunction "2_2") (pintype "passive"))
      (node (ref "SOCKET_6") (pin "5") (pinfunction "5_5") (pintype "passive"))
    )
    (net (code "151") (name "TLPORT_A_BITS_DATA[8]") (class "Default")
      (node (ref "JP20") (pin "3") (pinfunction "3_3") (pintype "passive"))
      (node (ref "SOCKET_6") (pin "4") (pinfunction "4_4") (pintype "passive"))
    )
    (net (code "152") (name "TLPORT_A_BITS_DATA[9]") (class "Default")
      (node (ref "JP20") (pin "4") (pinfunction "4_4") (pintype "passive"))
      (node (ref "SOCKET_6") (pin "3") (pinfunction "3_3") (pintype "passive"))
    )
    (net (code "153") (name "TLPORT_A_BITS_DATA[10]") (class "Default")
      (node (ref "JP20") (pin "5") (pinfunction "5_5") (pintype "passive"))
      (node (ref "SOCKET_6") (pin "2") (pinfunction "2_2") (pintype "passive"))
    )
    (net (code "154") (name "TLPORT_A_BITS_DATA[11]") (class "Default")
      (node (ref "JP20") (pin "6") (pinfunction "6_6") (pintype "passive"))
      (node (ref "SOCKET_6") (pin "1") (pinfunction "1_1") (pintype "passive"))
    )
    (net (code "155") (name "TLPORT_A_BITS_DATA[12]") (class "Default")
      (node (ref "JP20") (pin "7") (pinfunction "7_7") (pintype "passive"))
      (node (ref "SOCKET_5") (pin "32") (pinfunction "32_32") (pintype "passive"))
    )
    (net (code "156") (name "TLPORT_A_BITS_DATA[13]") (class "Default")
      (node (ref "JP20") (pin "8") (pinfunction "8_8") (pintype "passive"))
      (node (ref "SOCKET_5") (pin "31") (pinfunction "31_31") (pintype "passive"))
    )
    (net (code "157") (name "TLPORT_A_BITS_DATA[14]") (class "Default")
      (node (ref "JP20") (pin "9") (pinfunction "9_9") (pintype "passive"))
      (node (ref "SOCKET_5") (pin "29") (pinfunction "29_29") (pintype "passive"))
    )
    (net (code "158") (name "TLPORT_A_BITS_DATA[15]") (class "Default")
      (node (ref "JP20") (pin "10") (pinfunction "10_10") (pintype "passive"))
      (node (ref "SOCKET_5") (pin "28") (pinfunction "28_28") (pintype "passive"))
    )
    (net (code "159") (name "TLPORT_A_BITS_DATA[16]") (class "Default")
      (node (ref "JP19") (pin "31") (pinfunction "31_31") (pintype "passive"))
      (node (ref "SOCKET_5") (pin "27") (pinfunction "27_27") (pintype "passive"))
    )
    (net (code "160") (name "TLPORT_A_BITS_DATA[17]") (class "Default")
      (node (ref "JP19") (pin "32") (pinfunction "32_32") (pintype "passive"))
      (node (ref "SOCKET_5") (pin "26") (pinfunction "26_26") (pintype "passive"))
    )
    (net (code "161") (name "TLPORT_A_BITS_DATA[18]") (class "Default")
      (node (ref "JP19") (pin "33") (pinfunction "33_33") (pintype "passive"))
      (node (ref "SOCKET_5") (pin "25") (pinfunction "25_25") (pintype "passive"))
    )
    (net (code "162") (name "TLPORT_A_BITS_DATA[19]") (class "Default")
      (node (ref "JP19") (pin "34") (pinfunction "34_34") (pintype "passive"))
      (node (ref "SOCKET_5") (pin "23") (pinfunction "23_23") (pintype "passive"))
    )
    (net (code "163") (name "TLPORT_A_BITS_DATA[20]") (class "Default")
      (node (ref "JP19") (pin "35") (pinfunction "35_35") (pintype "passive"))
      (node (ref "SOCKET_5") (pin "22") (pinfunction "22_22") (pintype "passive"))
    )
    (net (code "164") (name "TLPORT_A_BITS_DATA[21]") (class "Default")
      (node (ref "JP19") (pin "36") (pinfunction "36_36") (pintype "passive"))
      (node (ref "SOCKET_5") (pin "21") (pinfunction "21_21") (pintype "passive"))
    )
    (net (code "165") (name "TLPORT_A_BITS_DATA[22]") (class "Default")
      (node (ref "JP19") (pin "37") (pinfunction "37_37") (pintype "passive"))
      (node (ref "SOCKET_5") (pin "20") (pinfunction "20_20") (pintype "passive"))
    )
    (net (code "166") (name "TLPORT_A_BITS_DATA[23]") (class "Default")
      (node (ref "JP19") (pin "38") (pinfunction "38_38") (pintype "passive"))
      (node (ref "SOCKET_5") (pin "19") (pinfunction "19_19") (pintype "passive"))
    )
    (net (code "167") (name "TLPORT_A_BITS_DATA[24]") (class "Default")
      (node (ref "JP19") (pin "39") (pinfunction "39_39") (pintype "passive"))
      (node (ref "SOCKET_5") (pin "18") (pinfunction "18_18") (pintype "passive"))
    )
    (net (code "168") (name "TLPORT_A_BITS_DATA[25]") (class "Default")
      (node (ref "JP19") (pin "40") (pinfunction "40_40") (pintype "passive"))
      (node (ref "SOCKET_5") (pin "17") (pinfunction "17_17") (pintype "passive"))
    )
    (net (code "169") (name "TLPORT_A_BITS_DATA[26]") (class "Default")
      (node (ref "JP19") (pin "28") (pinfunction "28_28") (pintype "passive"))
      (node (ref "SOCKET_5") (pin "15") (pinfunction "15_15") (pintype "passive"))
    )
    (net (code "170") (name "TLPORT_A_BITS_DATA[27]") (class "Default")
      (node (ref "JP19") (pin "27") (pinfunction "27_27") (pintype "passive"))
      (node (ref "SOCKET_5") (pin "14") (pinfunction "14_14") (pintype "passive"))
    )
    (net (code "171") (name "TLPORT_A_BITS_DATA[28]") (class "Default")
      (node (ref "JP19") (pin "26") (pinfunction "26_26") (pintype "passive"))
      (node (ref "SOCKET_5") (pin "13") (pinfunction "13_13") (pintype "passive"))
    )
    (net (code "172") (name "TLPORT_A_BITS_DATA[29]") (class "Default")
      (node (ref "JP19") (pin "25") (pinfunction "25_25") (pintype "passive"))
      (node (ref "SOCKET_5") (pin "12") (pinfunction "12_12") (pintype "passive"))
    )
    (net (code "173") (name "TLPORT_A_BITS_DATA[30]") (class "Default")
      (node (ref "JP19") (pin "24") (pinfunction "24_24") (pintype "passive"))
      (node (ref "SOCKET_5") (pin "10") (pinfunction "10_10") (pintype "passive"))
    )
    (net (code "174") (name "TLPORT_A_BITS_DATA[31]") (class "Default")
      (node (ref "JP19") (pin "23") (pinfunction "23_23") (pintype "passive"))
      (node (ref "SOCKET_5") (pin "9") (pinfunction "9_9") (pintype "passive"))
    )
    (net (code "175") (name "TLPORT_A_BITS_MASK[0]") (class "Default")
      (node (ref "JP19") (pin "22") (pinfunction "22_22") (pintype "passive"))
      (node (ref "SOCKET_5") (pin "8") (pinfunction "8_8") (pintype "passive"))
    )
    (net (code "176") (name "TLPORT_A_BITS_MASK[1]") (class "Default")
      (node (ref "JP19") (pin "21") (pinfunction "21_21") (pintype "passive"))
      (node (ref "SOCKET_5") (pin "7") (pinfunction "7_7") (pintype "passive"))
    )
    (net (code "177") (name "TLPORT_A_BITS_MASK[2]") (class "Default")
      (node (ref "JP19") (pin "20") (pinfunction "20_20") (pintype "passive"))
      (node (ref "SOCKET_4") (pin "25") (pinfunction "25_25") (pintype "passive"))
    )
    (net (code "178") (name "TLPORT_A_BITS_MASK[3]") (class "Default")
      (node (ref "JP19") (pin "19") (pinfunction "19_19") (pintype "passive"))
      (node (ref "SOCKET_4") (pin "24") (pinfunction "24_24") (pintype "passive"))
    )
    (net (code "179") (name "TLPORT_A_BITS_OPCODE[0]") (class "Default")
      (node (ref "JP18") (pin "8") (pinfunction "8_8") (pintype "passive"))
      (node (ref "SOCKET_2") (pin "24") (pinfunction "24_24") (pintype "passive"))
    )
    (net (code "180") (name "TLPORT_A_BITS_OPCODE[1]") (class "Default")
      (node (ref "JP18") (pin "7") (pinfunction "7_7") (pintype "passive"))
      (node (ref "SOCKET_2") (pin "23") (pinfunction "23_23") (pintype "passive"))
    )
    (net (code "181") (name "TLPORT_A_BITS_OPCODE[2]") (class "Default")
      (node (ref "JP18") (pin "3") (pinfunction "3_3") (pintype "passive"))
      (node (ref "SOCKET_2") (pin "21") (pinfunction "21_21") (pintype "passive"))
    )
    (net (code "182") (name "TLPORT_A_BITS_PARAM[0]") (class "Default")
      (node (ref "JP18") (pin "13") (pinfunction "13_13") (pintype "passive"))
      (node (ref "PARAM_0_SELECT") (pin "2") (pinfunction "2_2") (pintype "passive"))
      (node (ref "PARAM_0_SELECT") (pin "4") (pinfunction "4_4") (pintype "passive"))
    )
    (net (code "183") (name "TLPORT_A_BITS_PARAM[1]") (class "Default")
      (node (ref "JP18") (pin "10") (pinfunction "10_10") (pintype "passive"))
      (node (ref "SOCKET_2") (pin "26") (pinfunction "26_26") (pintype "passive"))
    )
    (net (code "184") (name "TLPORT_A_BITS_PARAM[2]") (class "Default")
      (node (ref "JP18") (pin "9") (pinfunction "9_9") (pintype "passive"))
      (node (ref "SOCKET_2") (pin "25") (pinfunction "25_25") (pintype "passive"))
    )
    (net (code "185") (name "TLPORT_A_BITS_SIZE[0]") (class "Default")
      (node (ref "JP18") (pin "16") (pinfunction "16_16") (pintype "passive"))
      (node (ref "SOCKET_3") (pin "9") (pinfunction "9_9") (pintype "passive"))
    )
    (net (code "186") (name "TLPORT_A_BITS_SIZE[1]") (class "Default")
      (node (ref "JP18") (pin "15") (pinfunction "15_15") (pintype "passive"))
      (node (ref "SOCKET_3") (pin "8") (pinfunction "8_8") (pintype "passive"))
    )
    (net (code "187") (name "TLPORT_A_BITS_SIZE[2]") (class "Default")
      (node (ref "JP18") (pin "14") (pinfunction "14_14") (pintype "passive"))
      (node (ref "SOCKET_3") (pin "7") (pinfunction "7_7") (pintype "passive"))
    )
    (net (code "188") (name "TLPORT_A_BITS_SOURCE[0]") (class "Default")
      (node (ref "JP18") (pin "22") (pinfunction "22_22") (pintype "passive"))
      (node (ref "SOCKET_3") (pin "17") (pinfunction "17_17") (pintype "passive"))
    )
    (net (code "189") (name "TLPORT_A_BITS_SOURCE[1]") (class "Default")
      (node (ref "JP18") (pin "21") (pinfunction "21_21") (pintype "passive"))
      (node (ref "SOCKET_3") (pin "15") (pinfunction "15_15") (pintype "passive"))
    )
    (net (code "190") (name "TLPORT_A_BITS_SOURCE[2]") (class "Default")
      (node (ref "JP18") (pin "20") (pinfunction "20_20") (pintype "passive"))
      (node (ref "SOCKET_3") (pin "14") (pinfunction "14_14") (pintype "passive"))
    )
    (net (code "191") (name "TLPORT_A_BITS_SOURCE[3]") (class "Default")
      (node (ref "JP18") (pin "19") (pinfunction "19_19") (pintype "passive"))
      (node (ref "SOCKET_3") (pin "13") (pinfunction "13_13") (pintype "passive"))
    )
    (net (code "192") (name "TLPORT_A_BITS_SOURCE[4]") (class "Default")
      (node (ref "JP18") (pin "18") (pinfunction "18_18") (pintype "passive"))
      (node (ref "SOCKET_3") (pin "12") (pinfunction "12_12") (pintype "passive"))
    )
    (net (code "193") (name "TLPORT_A_BITS_SOURCE[5]") (class "Default")
      (node (ref "JP18") (pin "17") (pinfunction "17_17") (pintype "passive"))
      (node (ref "SOCKET_3") (pin "10") (pinfunction "10_10") (pintype "passive"))
    )
    (net (code "194") (name "TLPORT_A_READY") (class "Default")
      (node (ref "JP18") (pin "4") (pinfunction "4_4") (pintype "passive"))
      (node (ref "SOCKET_2") (pin "18") (pinfunction "18_18") (pintype "passive"))
    )
    (net (code "195") (name "TLPORT_A_VALID") (class "Default")
      (node (ref "JP18") (pin "1") (pinfunction "1_1") (pintype "passive"))
      (node (ref "SOCKET_2") (pin "20") (pinfunction "20_20") (pintype "passive"))
    )
    (net (code "196") (name "TLPORT_D_BITS_CORRUPT") (class "Default")
      (node (ref "JP20") (pin "40") (pinfunction "40_40") (pintype "passive"))
      (node (ref "SOCKET_7") (pin "19") (pinfunction "19_19") (pintype "passive"))
    )
    (net (code "197") (name "TLPORT_D_BITS_DATA[0]") (class "Default")
      (node (ref "JP21") (pin "40") (pinfunction "40_40") (pintype "passive"))
      (node (ref "SOCKET_8") (pin "25") (pinfunction "25_25") (pintype "passive"))
    )
    (net (code "198") (name "TLPORT_D_BITS_DATA[1]") (class "Default")
      (node (ref "JP21") (pin "39") (pinfunction "39_39") (pintype "passive"))
      (node (ref "SOCKET_8") (pin "24") (pinfunction "24_24") (pintype "passive"))
    )
    (net (code "199") (name "TLPORT_D_BITS_DATA[2]") (class "Default")
      (node (ref "JP21") (pin "38") (pinfunction "38_38") (pintype "passive"))
      (node (ref "SOCKET_8") (pin "23") (pinfunction "23_23") (pintype "passive"))
    )
    (net (code "200") (name "TLPORT_D_BITS_DATA[3]") (class "Default")
      (node (ref "JP21") (pin "37") (pinfunction "37_37") (pintype "passive"))
      (node (ref "SOCKET_8") (pin "21") (pinfunction "21_21") (pintype "passive"))
    )
    (net (code "201") (name "TLPORT_D_BITS_DATA[4]") (class "Default")
      (node (ref "JP21") (pin "36") (pinfunction "36_36") (pintype "passive"))
      (node (ref "SOCKET_8") (pin "20") (pinfunction "20_20") (pintype "passive"))
    )
    (net (code "202") (name "TLPORT_D_BITS_DATA[5]") (class "Default")
      (node (ref "JP21") (pin "35") (pinfunction "35_35") (pintype "passive"))
      (node (ref "SOCKET_8") (pin "18") (pinfunction "18_18") (pintype "passive"))
    )
    (net (code "203") (name "TLPORT_D_BITS_DATA[6]") (class "Default")
      (node (ref "JP21") (pin "34") (pinfunction "34_34") (pintype "passive"))
      (node (ref "SOCKET_8") (pin "17") (pinfunction "17_17") (pintype "passive"))
    )
    (net (code "204") (name "TLPORT_D_BITS_DATA[7]") (class "Default")
      (node (ref "JP21") (pin "33") (pinfunction "33_33") (pintype "passive"))
      (node (ref "SOCKET_8") (pin "15") (pinfunction "15_15") (pintype "passive"))
    )
    (net (code "205") (name "TLPORT_D_BITS_DATA[8]") (class "Default")
      (node (ref "JP21") (pin "32") (pinfunction "32_32") (pintype "passive"))
      (node (ref "SOCKET_8") (pin "14") (pinfunction "14_14") (pintype "passive"))
    )
    (net (code "206") (name "TLPORT_D_BITS_DATA[9]") (class "Default")
      (node (ref "JP21") (pin "31") (pinfunction "31_31") (pintype "passive"))
      (node (ref "SOCKET_8") (pin "13") (pinfunction "13_13") (pintype "passive"))
    )
    (net (code "207") (name "TLPORT_D_BITS_DATA[10]") (class "Default")
      (node (ref "JP21") (pin "28") (pinfunction "28_28") (pintype "passive"))
      (node (ref "SOCKET_8") (pin "12") (pinfunction "12_12") (pintype "passive"))
    )
    (net (code "208") (name "TLPORT_D_BITS_DATA[11]") (class "Default")
      (node (ref "JP21") (pin "27") (pinfunction "27_27") (pintype "passive"))
      (node (ref "SOCKET_8") (pin "11") (pinfunction "11_11") (pintype "passive"))
    )
    (net (code "209") (name "TLPORT_D_BITS_DATA[12]") (class "Default")
      (node (ref "JP21") (pin "26") (pinfunction "26_26") (pintype "passive"))
      (node (ref "SOCKET_8") (pin "10") (pinfunction "10_10") (pintype "passive"))
    )
    (net (code "210") (name "TLPORT_D_BITS_DATA[13]") (class "Default")
      (node (ref "JP21") (pin "25") (pinfunction "25_25") (pintype "passive"))
      (node (ref "SOCKET_8") (pin "9") (pinfunction "9_9") (pintype "passive"))
    )
    (net (code "211") (name "TLPORT_D_BITS_DATA[14]") (class "Default")
      (node (ref "JP21") (pin "24") (pinfunction "24_24") (pintype "passive"))
      (node (ref "SOCKET_8") (pin "7") (pinfunction "7_7") (pintype "passive"))
    )
    (net (code "212") (name "TLPORT_D_BITS_DATA[15]") (class "Default")
      (node (ref "JP21") (pin "23") (pinfunction "23_23") (pintype "passive"))
      (node (ref "SOCKET_8") (pin "6") (pinfunction "6_6") (pintype "passive"))
    )
    (net (code "213") (name "TLPORT_D_BITS_DATA[16]") (class "Default")
      (node (ref "JP21") (pin "22") (pinfunction "22_22") (pintype "passive"))
      (node (ref "SOCKET_8") (pin "5") (pinfunction "5_5") (pintype "passive"))
    )
    (net (code "214") (name "TLPORT_D_BITS_DATA[17]") (class "Default")
      (node (ref "JP21") (pin "21") (pinfunction "21_21") (pintype "passive"))
      (node (ref "SOCKET_8") (pin "4") (pinfunction "4_4") (pintype "passive"))
    )
    (net (code "215") (name "TLPORT_D_BITS_DATA[18]") (class "Default")
      (node (ref "JP21") (pin "20") (pinfunction "20_20") (pintype "passive"))
      (node (ref "SOCKET_8") (pin "3") (pinfunction "3_3") (pintype "passive"))
    )
    (net (code "216") (name "TLPORT_D_BITS_DATA[19]") (class "Default")
      (node (ref "JP21") (pin "19") (pinfunction "19_19") (pintype "passive"))
      (node (ref "SOCKET_8") (pin "2") (pinfunction "2_2") (pintype "passive"))
    )
    (net (code "217") (name "TLPORT_D_BITS_DATA[20]") (class "Default")
      (node (ref "JP21") (pin "18") (pinfunction "18_18") (pintype "passive"))
      (node (ref "SOCKET_8") (pin "1") (pinfunction "1_1") (pintype "passive"))
    )
    (net (code "218") (name "TLPORT_D_BITS_DATA[21]") (class "Default")
      (node (ref "JP21") (pin "17") (pinfunction "17_17") (pintype "passive"))
      (node (ref "SOCKET_7") (pin "32") (pinfunction "32_32") (pintype "passive"))
    )
    (net (code "219") (name "TLPORT_D_BITS_DATA[22]") (class "Default")
      (node (ref "JP21") (pin "16") (pinfunction "16_16") (pintype "passive"))
      (node (ref "SOCKET_7") (pin "31") (pinfunction "31_31") (pintype "passive"))
    )
    (net (code "220") (name "TLPORT_D_BITS_DATA[23]") (class "Default")
      (node (ref "JP21") (pin "15") (pinfunction "15_15") (pintype "passive"))
      (node (ref "SOCKET_7") (pin "29") (pinfunction "29_29") (pintype "passive"))
    )
    (net (code "221") (name "TLPORT_D_BITS_DATA[24]") (class "Default")
      (node (ref "JP21") (pin "14") (pinfunction "14_14") (pintype "passive"))
      (node (ref "SOCKET_7") (pin "28") (pinfunction "28_28") (pintype "passive"))
    )
    (net (code "222") (name "TLPORT_D_BITS_DATA[25]") (class "Default")
      (node (ref "JP21") (pin "13") (pinfunction "13_13") (pintype "passive"))
      (node (ref "SOCKET_7") (pin "27") (pinfunction "27_27") (pintype "passive"))
    )
    (net (code "223") (name "TLPORT_D_BITS_DATA[26]") (class "Default")
      (node (ref "JP21") (pin "10") (pinfunction "10_10") (pintype "passive"))
      (node (ref "SOCKET_7") (pin "26") (pinfunction "26_26") (pintype "passive"))
    )
    (net (code "224") (name "TLPORT_D_BITS_DATA[27]") (class "Default")
      (node (ref "JP21") (pin "9") (pinfunction "9_9") (pintype "passive"))
      (node (ref "SOCKET_7") (pin "25") (pinfunction "25_25") (pintype "passive"))
    )
    (net (code "225") (name "TLPORT_D_BITS_DATA[28]") (class "Default")
      (node (ref "JP21") (pin "8") (pinfunction "8_8") (pintype "passive"))
      (node (ref "SOCKET_7") (pin "23") (pinfunction "23_23") (pintype "passive"))
    )
    (net (code "226") (name "TLPORT_D_BITS_DATA[29]") (class "Default")
      (node (ref "JP21") (pin "7") (pinfunction "7_7") (pintype "passive"))
      (node (ref "SOCKET_7") (pin "22") (pinfunction "22_22") (pintype "passive"))
    )
    (net (code "227") (name "TLPORT_D_BITS_DATA[30]") (class "Default")
      (node (ref "JP21") (pin "6") (pinfunction "6_6") (pintype "passive"))
      (node (ref "SOCKET_7") (pin "21") (pinfunction "21_21") (pintype "passive"))
    )
    (net (code "228") (name "TLPORT_D_BITS_DATA[31]") (class "Default")
      (node (ref "JP21") (pin "5") (pinfunction "5_5") (pintype "passive"))
      (node (ref "SOCKET_7") (pin "20") (pinfunction "20_20") (pintype "passive"))
    )
    (net (code "229") (name "TLPORT_D_BITS_DENIED") (class "Default")
      (node (ref "JP20") (pin "39") (pinfunction "39_39") (pintype "passive"))
      (node (ref "SOCKET_7") (pin "18") (pinfunction "18_18") (pintype "passive"))
    )
    (net (code "230") (name "TLPORT_D_BITS_OPCODE[0]") (class "Default")
      (node (ref "JP20") (pin "24") (pinfunction "24_24") (pintype "passive"))
      (node (ref "SOCKET_6") (pin "21") (pinfunction "21_21") (pintype "passive"))
    )
    (net (code "231") (name "TLPORT_D_BITS_OPCODE[1]") (class "Default")
      (node (ref "JP20") (pin "23") (pinfunction "23_23") (pintype "passive"))
      (node (ref "SOCKET_6") (pin "20") (pinfunction "20_20") (pintype "passive"))
    )
    (net (code "232") (name "TLPORT_D_BITS_OPCODE[2]") (class "Default")
      (node (ref "JP20") (pin "22") (pinfunction "22_22") (pintype "passive"))
      (node (ref "SOCKET_6") (pin "18") (pinfunction "18_18") (pintype "passive"))
    )
    (net (code "233") (name "TLPORT_D_BITS_PARAM[0]") (class "Default")
      (node (ref "JP20") (pin "26") (pinfunction "26_26") (pintype "passive"))
      (node (ref "SOCKET_6") (pin "24") (pinfunction "24_24") (pintype "passive"))
    )
    (net (code "234") (name "TLPORT_D_BITS_PARAM[1]") (class "Default")
      (node (ref "JP20") (pin "25") (pinfunction "25_25") (pintype "passive"))
      (node (ref "SOCKET_6") (pin "23") (pinfunction "23_23") (pintype "passive"))
    )
    (net (code "235") (name "TLPORT_D_BITS_SINK") (class "Default")
      (node (ref "JP20") (pin "38") (pinfunction "38_38") (pintype "passive"))
      (node (ref "SOCKET_7") (pin "17") (pinfunction "17_17") (pintype "passive"))
    )
    (net (code "236") (name "TLPORT_D_BITS_SIZE[0]") (class "Default")
      (node (ref "JP20") (pin "31") (pinfunction "31_31") (pintype "passive"))
      (node (ref "SOCKET_7") (pin "8") (pinfunction "8_8") (pintype "passive"))
    )
    (net (code "237") (name "TLPORT_D_BITS_SIZE[1]") (class "Default")
      (node (ref "JP20") (pin "28") (pinfunction "28_28") (pintype "passive"))
      (node (ref "SOCKET_7") (pin "7") (pinfunction "7_7") (pintype "passive"))
    )
    (net (code "238") (name "TLPORT_D_BITS_SIZE[2]") (class "Default")
      (node (ref "JP20") (pin "27") (pinfunction "27_27") (pintype "passive"))
      (node (ref "SOCKET_6") (pin "25") (pinfunction "25_25") (pintype "passive"))
    )
    (net (code "239") (name "TLPORT_D_BITS_SOURCE[0]") (class "Default")
      (node (ref "JP20") (pin "37") (pinfunction "37_37") (pintype "passive"))
      (node (ref "SOCKET_7") (pin "15") (pinfunction "15_15") (pintype "passive"))
    )
    (net (code "240") (name "TLPORT_D_BITS_SOURCE[1]") (class "Default")
      (node (ref "JP20") (pin "36") (pinfunction "36_36") (pintype "passive"))
      (node (ref "SOCKET_7") (pin "14") (pinfunction "14_14") (pintype "passive"))
    )
    (net (code "241") (name "TLPORT_D_BITS_SOURCE[2]") (class "Default")
      (node (ref "JP20") (pin "35") (pinfunction "35_35") (pintype "passive"))
      (node (ref "SOCKET_7") (pin "13") (pinfunction "13_13") (pintype "passive"))
    )
    (net (code "242") (name "TLPORT_D_BITS_SOURCE[3]") (class "Default")
      (node (ref "JP20") (pin "34") (pinfunction "34_34") (pintype "passive"))
      (node (ref "SOCKET_7") (pin "12") (pinfunction "12_12") (pintype "passive"))
    )
    (net (code "243") (name "TLPORT_D_BITS_SOURCE[4]") (class "Default")
      (node (ref "JP20") (pin "33") (pinfunction "33_33") (pintype "passive"))
      (node (ref "SOCKET_7") (pin "10") (pinfunction "10_10") (pintype "passive"))
    )
    (net (code "244") (name "TLPORT_D_BITS_SOURCE[5]") (class "Default")
      (node (ref "JP20") (pin "32") (pinfunction "32_32") (pintype "passive"))
      (node (ref "SOCKET_7") (pin "9") (pinfunction "9_9") (pintype "passive"))
    )
    (net (code "245") (name "TLPORT_D_READY") (class "Default")
      (node (ref "JP20") (pin "20") (pinfunction "20_20") (pintype "passive"))
      (node (ref "SOCKET_6") (pin "15") (pinfunction "15_15") (pintype "passive"))
    )
    (net (code "246") (name "TLPORT_D_VALID") (class "Default")
      (node (ref "JP20") (pin "21") (pinfunction "21_21") (pintype "passive"))
      (node (ref "SOCKET_6") (pin "17") (pinfunction "17_17") (pintype "passive"))
    )
    (net (code "247") (name "TMS") (class "Default")
      (node (ref "IC3") (pin "11") (pinfunction "B2_11") (pintype "bidirectional"))
      (node (ref "JTAG_20_PIN") (pin "7") (pinfunction "7_7") (pintype "passive"))
      (node (ref "R22") (pin "1") (pinfunction "1_1") (pintype "passive"))
    )
    (net (code "248") (name "UART_RXD") (class "Default")
      (node (ref "SOCKET_2") (pin "4") (pinfunction "4_4") (pintype "passive"))
      (node (ref "USB-UART") (pin "3") (pinfunction "3_3") (pintype "passive"))
    )
    (net (code "249") (name "UART_TXD") (class "Default")
      (node (ref "SOCKET_2") (pin "3") (pinfunction "3_3") (pintype "passive"))
      (node (ref "USB-UART") (pin "7") (pinfunction "7_7") (pintype "passive"))
    )
    (net (code "250") (name "USBCLK") (class "Default")
      (node (ref "SOCKET_8") (pin "26") (pinfunction "26_26") (pintype "passive"))
    )
    (net (code "251") (name "USBFULLSPEED") (class "Default")
      (node (ref "SOCKET_1") (pin "6") (pinfunction "6_6") (pintype "passive"))
    )
    (net (code "252") (name "USBWIRECTRLOUT") (class "Default")
      (node (ref "SOCKET_1") (pin "4") (pinfunction "4_4") (pintype "passive"))
    )
    (net (code "253") (name "USBWIREDATAIN[0]") (class "Default")
      (node (ref "SOCKET_8") (pin "30") (pinfunction "30_30") (pintype "passive"))
    )
    (net (code "254") (name "USBWIREDATAIN[1]") (class "Default")
      (node (ref "SOCKET_8") (pin "28") (pinfunction "28_28") (pintype "passive"))
    )
    (net (code "255") (name "USBWIREDATAOUT[0]") (class "Default")
      (node (ref "SOCKET_1") (pin "2") (pinfunction "2_2") (pintype "passive"))
    )
    (net (code "256") (name "USBWIREDATAOUT[1]") (class "Default")
      (node (ref "SOCKET_8") (pin "32") (pinfunction "32_32") (pintype "passive"))
    )
    (net (code "257") (name "VDD_1.8_1") (class "Default")
      (node (ref "C14") (pin "1") (pinfunction "1_1") (pintype "passive"))
      (node (ref "IC7") (pin "2") (pinfunction "OUTPUT_2") (pintype "bidirectional"))
      (node (ref "IC7") (pin "4") (pinfunction "VOUT_4") (pintype "bidirectional"))
      (node (ref "JP8") (pin "1") (pinfunction "1_1") (pintype "passive"))
      (node (ref "Q3") (pin "1") (pinfunction "G_1") (pintype "bidirectional"))
      (node (ref "R1") (pin "2") (pinfunction "2_2") (pintype "passive"))
      (node (ref "R63") (pin "2") (pinfunction "2_2") (pintype "passive"))
    )
    (net (code "258") (name "VDD_1.8_2") (class "Default")
      (node (ref "C16") (pin "1") (pinfunction "1_1") (pintype "passive"))
      (node (ref "IC8") (pin "2") (pinfunction "OUTPUT_2") (pintype "bidirectional"))
      (node (ref "IC8") (pin "4") (pinfunction "VOUT_4") (pintype "bidirectional"))
      (node (ref "JP8") (pin "5") (pinfunction "5_5") (pintype "passive"))
      (node (ref "Q4") (pin "1") (pinfunction "G_1") (pintype "bidirectional"))
      (node (ref "R3") (pin "2") (pinfunction "2_2") (pintype "passive"))
      (node (ref "R61") (pin "2") (pinfunction "2_2") (pintype "passive"))
    )
    (net (code "259") (name "VDD_1.8_3") (class "Default")
      (node (ref "C18") (pin "1") (pinfunction "1_1") (pintype "passive"))
      (node (ref "IC9") (pin "2") (pinfunction "OUTPUT_2") (pintype "bidirectional"))
      (node (ref "IC9") (pin "4") (pinfunction "VOUT_4") (pintype "bidirectional"))
      (node (ref "JP8") (pin "7") (pinfunction "7_7") (pintype "passive"))
      (node (ref "Q5") (pin "1") (pinfunction "G_1") (pintype "bidirectional"))
      (node (ref "R5") (pin "2") (pinfunction "2_2") (pintype "passive"))
      (node (ref "R62") (pin "2") (pinfunction "2_2") (pintype "passive"))
    )
    (net (code "260") (name "VDD_1V8") (class "Default")
      (node (ref "C3") (pin "1") (pinfunction "1_1") (pintype "passive"))
      (node (ref "C5") (pin "1") (pinfunction "1_1") (pintype "passive"))
      (node (ref "C6") (pin "1") (pinfunction "1_1") (pintype "passive"))
      (node (ref "IC1") (pin "14") (pinfunction "VCCA_14") (pintype "bidirectional"))
      (node (ref "IC1") (pin "15") (pinfunction "DIR1_15") (pintype "bidirectional"))
      (node (ref "IC1") (pin "5") (pinfunction "DIR3_5") (pintype "bidirectional"))
      (node (ref "IC1") (pin "6") (pinfunction "DIR4_6") (pintype "bidirectional"))
      (node (ref "IC2") (pin "14") (pinfunction "VCCA_14") (pintype "bidirectional"))
      (node (ref "IC2") (pin "15") (pinfunction "DIR1_15") (pintype "bidirectional"))
      (node (ref "IC2") (pin "16") (pinfunction "DIR2_16") (pintype "bidirectional"))
      (node (ref "IC2") (pin "5") (pinfunction "DIR3_5") (pintype "bidirectional"))
      (node (ref "IC3") (pin "14") (pinfunction "VCCA_14") (pintype "bidirectional"))
      (node (ref "IC3") (pin "6") (pinfunction "DIR4_6") (pintype "bidirectional"))
      (node (ref "JP8") (pin "2") (pinfunction "2_2") (pintype "passive"))
      (node (ref "R26") (pin "2") (pinfunction "2_2") (pintype "passive"))
      (node (ref "R27") (pin "2") (pinfunction "2_2") (pintype "passive"))
      (node (ref "R28") (pin "2") (pinfunction "2_2") (pintype "passive"))
      (node (ref "R29") (pin "2") (pinfunction "2_2") (pintype "passive"))
      (node (ref "R30") (pin "2") (pinfunction "2_2") (pintype "passive"))
      (node (ref "R31") (pin "2") (pinfunction "2_2") (pintype "passive"))
      (node (ref "R32") (pin "2") (pinfunction "2_2") (pintype "passive"))
      (node (ref "R33") (pin "2") (pinfunction "2_2") (pintype "passive"))
      (node (ref "R58") (pin "2") (pinfunction "2_2") (pintype "passive"))
      (node (ref "R59") (pin "2") (pinfunction "2_2") (pintype "passive"))
      (node (ref "R60") (pin "2") (pinfunction "2_2") (pintype "passive"))
      (node (ref "USB-UART") (pin "5") (pinfunction "5_5") (pintype "passive"))
    )
    (net (code "261") (name "VDD_3V3") (class "Default")
      (node (ref "C1") (pin "1") (pinfunction "1_1") (pintype "passive"))
      (node (ref "C13") (pin "1") (pinfunction "1_1") (pintype "passive"))
      (node (ref "C15") (pin "1") (pinfunction "1_1") (pintype "passive"))
      (node (ref "C17") (pin "1") (pinfunction "1_1") (pintype "passive"))
      (node (ref "C2") (pin "1") (pinfunction "1_1") (pintype "passive"))
      (node (ref "C4") (pin "1") (pinfunction "1_1") (pintype "passive"))
      (node (ref "FLASH") (pin "1") (pinfunction "1_1") (pintype "passive"))
      (node (ref "FLASH") (pin "2") (pinfunction "2_2") (pintype "passive"))
      (node (ref "IC1") (pin "13") (pinfunction "VCCB_13") (pintype "bidirectional"))
      (node (ref "IC2") (pin "13") (pinfunction "VCCB_13") (pintype "bidirectional"))
      (node (ref "IC3") (pin "13") (pinfunction "VCCB_13") (pintype "bidirectional"))
      (node (ref "IC7") (pin "3") (pinfunction "INPUT_3") (pintype "bidirectional"))
      (node (ref "IC8") (pin "3") (pinfunction "INPUT_3") (pintype "bidirectional"))
      (node (ref "IC9") (pin "3") (pinfunction "INPUT_3") (pintype "bidirectional"))
      (node (ref "JP8") (pin "3") (pinfunction "3_3") (pintype "passive"))
      (node (ref "JTAG_20_PIN") (pin "1") (pinfunction "1_1") (pintype "passive"))
      (node (ref "JTAG_20_PIN") (pin "2") (pinfunction "2_2") (pintype "passive"))
      (node (ref "R22") (pin "2") (pinfunction "2_2") (pintype "passive"))
      (node (ref "R23") (pin "2") (pinfunction "2_2") (pintype "passive"))
      (node (ref "R24") (pin "2") (pinfunction "2_2") (pintype "passive"))
      (node (ref "R25") (pin "2") (pinfunction "2_2") (pintype "passive"))
      (node (ref "R46") (pin "2") (pinfunction "2_2") (pintype "passive"))
      (node (ref "R47") (pin "2") (pinfunction "2_2") (pintype "passive"))
      (node (ref "R48") (pin "2") (pinfunction "2_2") (pintype "passive"))
      (node (ref "R49") (pin "2") (pinfunction "2_2") (pintype "passive"))
      (node (ref "R50") (pin "2") (pinfunction "2_2") (pintype "passive"))
      (node (ref "R51") (pin "2") (pinfunction "2_2") (pintype "passive"))
      (node (ref "R52") (pin "2") (pinfunction "2_2") (pintype "passive"))
      (node (ref "R53") (pin "2") (pinfunction "2_2") (pintype "passive"))
      (node (ref "R54") (pin "2") (pinfunction "2_2") (pintype "passive"))
      (node (ref "R55") (pin "2") (pinfunction "2_2") (pintype "passive"))
      (node (ref "R56") (pin "2") (pinfunction "2_2") (pintype "passive"))
      (node (ref "R57") (pin "2") (pinfunction "2_2") (pintype "passive"))
      (node (ref "SD_CARD") (pin "1") (pinfunction "1_1") (pintype "passive"))
      (node (ref "SD_CARD") (pin "2") (pinfunction "2_2") (pintype "passive"))
    )
    (net (code "262") (name "VDD_3V3_GPIO") (class "Default")
      (node (ref "JP18") (pin "29") (pinfunction "29_29") (pintype "passive"))
      (node (ref "JP19") (pin "29") (pinfunction "29_29") (pintype "passive"))
      (node (ref "JP20") (pin "29") (pinfunction "29_29") (pintype "passive"))
      (node (ref "JP21") (pin "29") (pinfunction "29_29") (pintype "passive"))
      (node (ref "JP8") (pin "4") (pinfunction "4_4") (pintype "passive"))
    )
    (net (code "263") (name "VDD_CHIP") (class "Default")
      (node (ref "C19") (pin "1") (pinfunction "1_1") (pintype "passive"))
      (node (ref "C20") (pin "1") (pinfunction "1_1") (pintype "passive"))
      (node (ref "JP8") (pin "6") (pinfunction "6_6") (pintype "passive"))
      (node (ref "SOCKET_1") (pin "16") (pinfunction "16_16") (pintype "passive"))
      (node (ref "SOCKET_2") (pin "16") (pinfunction "16_16") (pintype "passive"))
      (node (ref "SOCKET_3") (pin "16") (pinfunction "16_16") (pintype "passive"))
      (node (ref "SOCKET_4") (pin "16") (pinfunction "16_16") (pintype "passive"))
      (node (ref "SOCKET_5") (pin "16") (pinfunction "16_16") (pintype "passive"))
      (node (ref "SOCKET_6") (pin "16") (pinfunction "16_16") (pintype "passive"))
      (node (ref "SOCKET_7") (pin "16") (pinfunction "16_16") (pintype "passive"))
      (node (ref "SOCKET_8") (pin "16") (pinfunction "16_16") (pintype "passive"))
    )
    (net (code "264") (name "VDD_CHIP_IO") (class "Default")
      (node (ref "C21") (pin "1") (pinfunction "1_1") (pintype "passive"))
      (node (ref "C22") (pin "1") (pinfunction "1_1") (pintype "passive"))
      (node (ref "JP8") (pin "8") (pinfunction "8_8") (pintype "passive"))
      (node (ref "SOCKET_1") (pin "24") (pinfunction "24_24") (pintype "passive"))
      (node (ref "SOCKET_2") (pin "19") (pinfunction "19_19") (pintype "passive"))
      (node (ref "SOCKET_3") (pin "24") (pinfunction "24_24") (pintype "passive"))
      (node (ref "SOCKET_4") (pin "19") (pinfunction "19_19") (pintype "passive"))
      (node (ref "SOCKET_5") (pin "24") (pinfunction "24_24") (pintype "passive"))
      (node (ref "SOCKET_6") (pin "19") (pinfunction "19_19") (pintype "passive"))
      (node (ref "SOCKET_7") (pin "24") (pinfunction "24_24") (pintype "passive"))
      (node (ref "SOCKET_8") (pin "19") (pinfunction "19_19") (pintype "passive"))
    )
    (net (code "265") (name "unconnected-(FLASH-Pad5)") (class "Default")
      (node (ref "FLASH") (pin "5") (pinfunction "5_5") (pintype "passive"))
    )
    (net (code "266") (name "unconnected-(FLASH-Pad7)") (class "Default")
      (node (ref "FLASH") (pin "7") (pinfunction "7_7") (pintype "passive"))
    )
    (net (code "267") (name "unconnected-(FLASH-Pad9)") (class "Default")
      (node (ref "FLASH") (pin "9") (pinfunction "9_9") (pintype "passive"))
    )
    (net (code "268") (name "unconnected-(FLASH-Pad11)") (class "Default")
      (node (ref "FLASH") (pin "11") (pinfunction "11_11") (pintype "passive"))
    )
    (net (code "269") (name "unconnected-(JP18-Pad11)") (class "Default")
      (node (ref "JP18") (pin "11") (pinfunction "11_11") (pintype "passive"))
    )
    (net (code "270") (name "unconnected-(JP19-Pad11)") (class "Default")
      (node (ref "JP19") (pin "11") (pinfunction "11_11") (pintype "passive"))
    )
    (net (code "271") (name "unconnected-(JP20-Pad11)") (class "Default")
      (node (ref "JP20") (pin "11") (pinfunction "11_11") (pintype "passive"))
    )
    (net (code "272") (name "unconnected-(JP21-Pad1)") (class "Default")
      (node (ref "JP21") (pin "1") (pinfunction "1_1") (pintype "passive"))
    )
    (net (code "273") (name "unconnected-(JP21-Pad3)") (class "Default")
      (node (ref "JP21") (pin "3") (pinfunction "3_3") (pintype "passive"))
    )
    (net (code "274") (name "unconnected-(JP21-Pad11)") (class "Default")
      (node (ref "JP21") (pin "11") (pinfunction "11_11") (pintype "passive"))
    )
    (net (code "275") (name "unconnected-(JTAG_20_PIN-Pad3)") (class "Default")
      (node (ref "JTAG_20_PIN") (pin "3") (pinfunction "3_3") (pintype "passive"))
    )
    (net (code "276") (name "unconnected-(JTAG_20_PIN-Pad11)") (class "Default")
      (node (ref "JTAG_20_PIN") (pin "11") (pinfunction "11_11") (pintype "passive"))
    )
    (net (code "277") (name "unconnected-(JTAG_20_PIN-Pad15)") (class "Default")
      (node (ref "JTAG_20_PIN") (pin "15") (pinfunction "15_15") (pintype "passive"))
    )
    (net (code "278") (name "unconnected-(JTAG_20_PIN-Pad17)") (class "Default")
      (node (ref "JTAG_20_PIN") (pin "17") (pinfunction "17_17") (pintype "passive"))
    )
    (net (code "279") (name "unconnected-(JTAG_20_PIN-Pad19)") (class "Default")
      (node (ref "JTAG_20_PIN") (pin "19") (pinfunction "19_19") (pintype "passive"))
    )
    (net (code "280") (name "unconnected-(SD_CARD-Pad5)") (class "Default")
      (node (ref "SD_CARD") (pin "5") (pinfunction "5_5") (pintype "passive"))
    )
    (net (code "281") (name "unconnected-(SD_CARD-Pad7)") (class "Default")
      (node (ref "SD_CARD") (pin "7") (pinfunction "7_7") (pintype "passive"))
    )
    (net (code "282") (name "unconnected-(SD_CARD-Pad9)") (class "Default")
      (node (ref "SD_CARD") (pin "9") (pinfunction "9_9") (pintype "passive"))
    )
    (net (code "283") (name "unconnected-(SD_CARD-Pad11)") (class "Default")
      (node (ref "SD_CARD") (pin "11") (pinfunction "11_11") (pintype "passive"))
    )
    (net (code "284") (name "unconnected-(SOCKET_1-Pad1)") (class "Default")
      (node (ref "SOCKET_1") (pin "1") (pinfunction "1_1") (pintype "passive"))
    )
    (net (code "285") (name "unconnected-(SOCKET_1-Pad3)") (class "Default")
      (node (ref "SOCKET_1") (pin "3") (pinfunction "3_3") (pintype "passive"))
    )
    (net (code "286") (name "unconnected-(SOCKET_1-Pad5)") (class "Default")
      (node (ref "SOCKET_1") (pin "5") (pinfunction "5_5") (pintype "passive"))
    )
    (net (code "287") (name "unconnected-(SOCKET_2-Pad12)") (class "Default")
      (node (ref "SOCKET_2") (pin "12") (pinfunction "12_12") (pintype "passive"))
    )
    (net (code "288") (name "unconnected-(SOCKET_2-Pad13)") (class "Default")
      (node (ref "SOCKET_2") (pin "13") (pinfunction "13_13") (pintype "passive"))
    )
    (net (code "289") (name "unconnected-(SOCKET_2-Pad29)") (class "Default")
      (node (ref "SOCKET_2") (pin "29") (pinfunction "29_29") (pintype "passive"))
    )
    (net (code "290") (name "unconnected-(SOCKET_2-Pad30)") (class "Default")
      (node (ref "SOCKET_2") (pin "30") (pinfunction "30_30") (pintype "passive"))
    )
    (net (code "291") (name "unconnected-(SOCKET_2-Pad31)") (class "Default")
      (node (ref "SOCKET_2") (pin "31") (pinfunction "31_31") (pintype "passive"))
    )
    (net (code "292") (name "unconnected-(SOCKET_2-Pad32)") (class "Default")
      (node (ref "SOCKET_2") (pin "32") (pinfunction "32_32") (pintype "passive"))
    )
    (net (code "293") (name "unconnected-(SOCKET_3-Pad1)") (class "Default")
      (node (ref "SOCKET_3") (pin "1") (pinfunction "1_1") (pintype "passive"))
    )
    (net (code "294") (name "unconnected-(SOCKET_3-Pad2)") (class "Default")
      (node (ref "SOCKET_3") (pin "2") (pinfunction "2_2") (pintype "passive"))
    )
    (net (code "295") (name "unconnected-(SOCKET_3-Pad3)") (class "Default")
      (node (ref "SOCKET_3") (pin "3") (pinfunction "3_3") (pintype "passive"))
    )
    (net (code "296") (name "unconnected-(SOCKET_3-Pad4)") (class "Default")
      (node (ref "SOCKET_3") (pin "4") (pinfunction "4_4") (pintype "passive"))
    )
    (net (code "297") (name "unconnected-(SOCKET_3-Pad5)") (class "Default")
      (node (ref "SOCKET_3") (pin "5") (pinfunction "5_5") (pintype "passive"))
    )
    (net (code "298") (name "unconnected-(SOCKET_3-Pad6)") (class "Default")
      (node (ref "SOCKET_3") (pin "6") (pinfunction "6_6") (pintype "passive"))
    )
    (net (code "299") (name "unconnected-(SOCKET_4-Pad26)") (class "Default")
      (node (ref "SOCKET_4") (pin "26") (pinfunction "26_26") (pintype "passive"))
    )
    (net (code "300") (name "unconnected-(SOCKET_4-Pad27)") (class "Default")
      (node (ref "SOCKET_4") (pin "27") (pinfunction "27_27") (pintype "passive"))
    )
    (net (code "301") (name "unconnected-(SOCKET_4-Pad28)") (class "Default")
      (node (ref "SOCKET_4") (pin "28") (pinfunction "28_28") (pintype "passive"))
    )
    (net (code "302") (name "unconnected-(SOCKET_4-Pad29)") (class "Default")
      (node (ref "SOCKET_4") (pin "29") (pinfunction "29_29") (pintype "passive"))
    )
    (net (code "303") (name "unconnected-(SOCKET_4-Pad30)") (class "Default")
      (node (ref "SOCKET_4") (pin "30") (pinfunction "30_30") (pintype "passive"))
    )
    (net (code "304") (name "unconnected-(SOCKET_4-Pad31)") (class "Default")
      (node (ref "SOCKET_4") (pin "31") (pinfunction "31_31") (pintype "passive"))
    )
    (net (code "305") (name "unconnected-(SOCKET_4-Pad32)") (class "Default")
      (node (ref "SOCKET_4") (pin "32") (pinfunction "32_32") (pintype "passive"))
    )
    (net (code "306") (name "unconnected-(SOCKET_5-Pad1)") (class "Default")
      (node (ref "SOCKET_5") (pin "1") (pinfunction "1_1") (pintype "passive"))
    )
    (net (code "307") (name "unconnected-(SOCKET_5-Pad2)") (class "Default")
      (node (ref "SOCKET_5") (pin "2") (pinfunction "2_2") (pintype "passive"))
    )
    (net (code "308") (name "unconnected-(SOCKET_5-Pad3)") (class "Default")
      (node (ref "SOCKET_5") (pin "3") (pinfunction "3_3") (pintype "passive"))
    )
    (net (code "309") (name "unconnected-(SOCKET_5-Pad4)") (class "Default")
      (node (ref "SOCKET_5") (pin "4") (pinfunction "4_4") (pintype "passive"))
    )
    (net (code "310") (name "unconnected-(SOCKET_5-Pad5)") (class "Default")
      (node (ref "SOCKET_5") (pin "5") (pinfunction "5_5") (pintype "passive"))
    )
    (net (code "311") (name "unconnected-(SOCKET_5-Pad6)") (class "Default")
      (node (ref "SOCKET_5") (pin "6") (pinfunction "6_6") (pintype "passive"))
    )
    (net (code "312") (name "unconnected-(SOCKET_6-Pad26)") (class "Default")
      (node (ref "SOCKET_6") (pin "26") (pinfunction "26_26") (pintype "passive"))
    )
    (net (code "313") (name "unconnected-(SOCKET_6-Pad27)") (class "Default")
      (node (ref "SOCKET_6") (pin "27") (pinfunction "27_27") (pintype "passive"))
    )
    (net (code "314") (name "unconnected-(SOCKET_6-Pad28)") (class "Default")
      (node (ref "SOCKET_6") (pin "28") (pinfunction "28_28") (pintype "passive"))
    )
    (net (code "315") (name "unconnected-(SOCKET_6-Pad29)") (class "Default")
      (node (ref "SOCKET_6") (pin "29") (pinfunction "29_29") (pintype "passive"))
    )
    (net (code "316") (name "unconnected-(SOCKET_6-Pad30)") (class "Default")
      (node (ref "SOCKET_6") (pin "30") (pinfunction "30_30") (pintype "passive"))
    )
    (net (code "317") (name "unconnected-(SOCKET_6-Pad31)") (class "Default")
      (node (ref "SOCKET_6") (pin "31") (pinfunction "31_31") (pintype "passive"))
    )
    (net (code "318") (name "unconnected-(SOCKET_6-Pad32)") (class "Default")
      (node (ref "SOCKET_6") (pin "32") (pinfunction "32_32") (pintype "passive"))
    )
    (net (code "319") (name "unconnected-(SOCKET_7-Pad1)") (class "Default")
      (node (ref "SOCKET_7") (pin "1") (pinfunction "1_1") (pintype "passive"))
    )
    (net (code "320") (name "unconnected-(SOCKET_7-Pad2)") (class "Default")
      (node (ref "SOCKET_7") (pin "2") (pinfunction "2_2") (pintype "passive"))
    )
    (net (code "321") (name "unconnected-(SOCKET_7-Pad3)") (class "Default")
      (node (ref "SOCKET_7") (pin "3") (pinfunction "3_3") (pintype "passive"))
    )
    (net (code "322") (name "unconnected-(SOCKET_7-Pad4)") (class "Default")
      (node (ref "SOCKET_7") (pin "4") (pinfunction "4_4") (pintype "passive"))
    )
    (net (code "323") (name "unconnected-(SOCKET_7-Pad5)") (class "Default")
      (node (ref "SOCKET_7") (pin "5") (pinfunction "5_5") (pintype "passive"))
    )
    (net (code "324") (name "unconnected-(SOCKET_7-Pad6)") (class "Default")
      (node (ref "SOCKET_7") (pin "6") (pinfunction "6_6") (pintype "passive"))
    )
    (net (code "325") (name "unconnected-(SOCKET_8-Pad27)") (class "Default")
      (node (ref "SOCKET_8") (pin "27") (pinfunction "27_27") (pintype "passive"))
    )
    (net (code "326") (name "unconnected-(SOCKET_8-Pad29)") (class "Default")
      (node (ref "SOCKET_8") (pin "29") (pinfunction "29_29") (pintype "passive"))
    )
    (net (code "327") (name "unconnected-(SOCKET_8-Pad31)") (class "Default")
      (node (ref "SOCKET_8") (pin "31") (pinfunction "31_31") (pintype "passive"))
    )
    (net (code "328") (name "unconnected-(USB-UART-Pad2)") (class "Default")
      (node (ref "USB-UART") (pin "2") (pinfunction "2_2") (pintype "passive"))
    )
    (net (code "329") (name "unconnected-(USB-UART-Pad4)") (class "Default")
      (node (ref "USB-UART") (pin "4") (pinfunction "4_4") (pintype "passive"))
    )
    (net (code "330") (name "unconnected-(USB-UART-Pad6)") (class "Default")
      (node (ref "USB-UART") (pin "6") (pinfunction "6_6") (pintype "passive"))
    )
    (net (code "331") (name "unconnected-(USB-UART-Pad8)") (class "Default")
      (node (ref "USB-UART") (pin "8") (pinfunction "8_8") (pintype "passive"))
    )
  )
)
